# shelves_v05.net
KiCad netlist of a schematic drawn in EAGLE
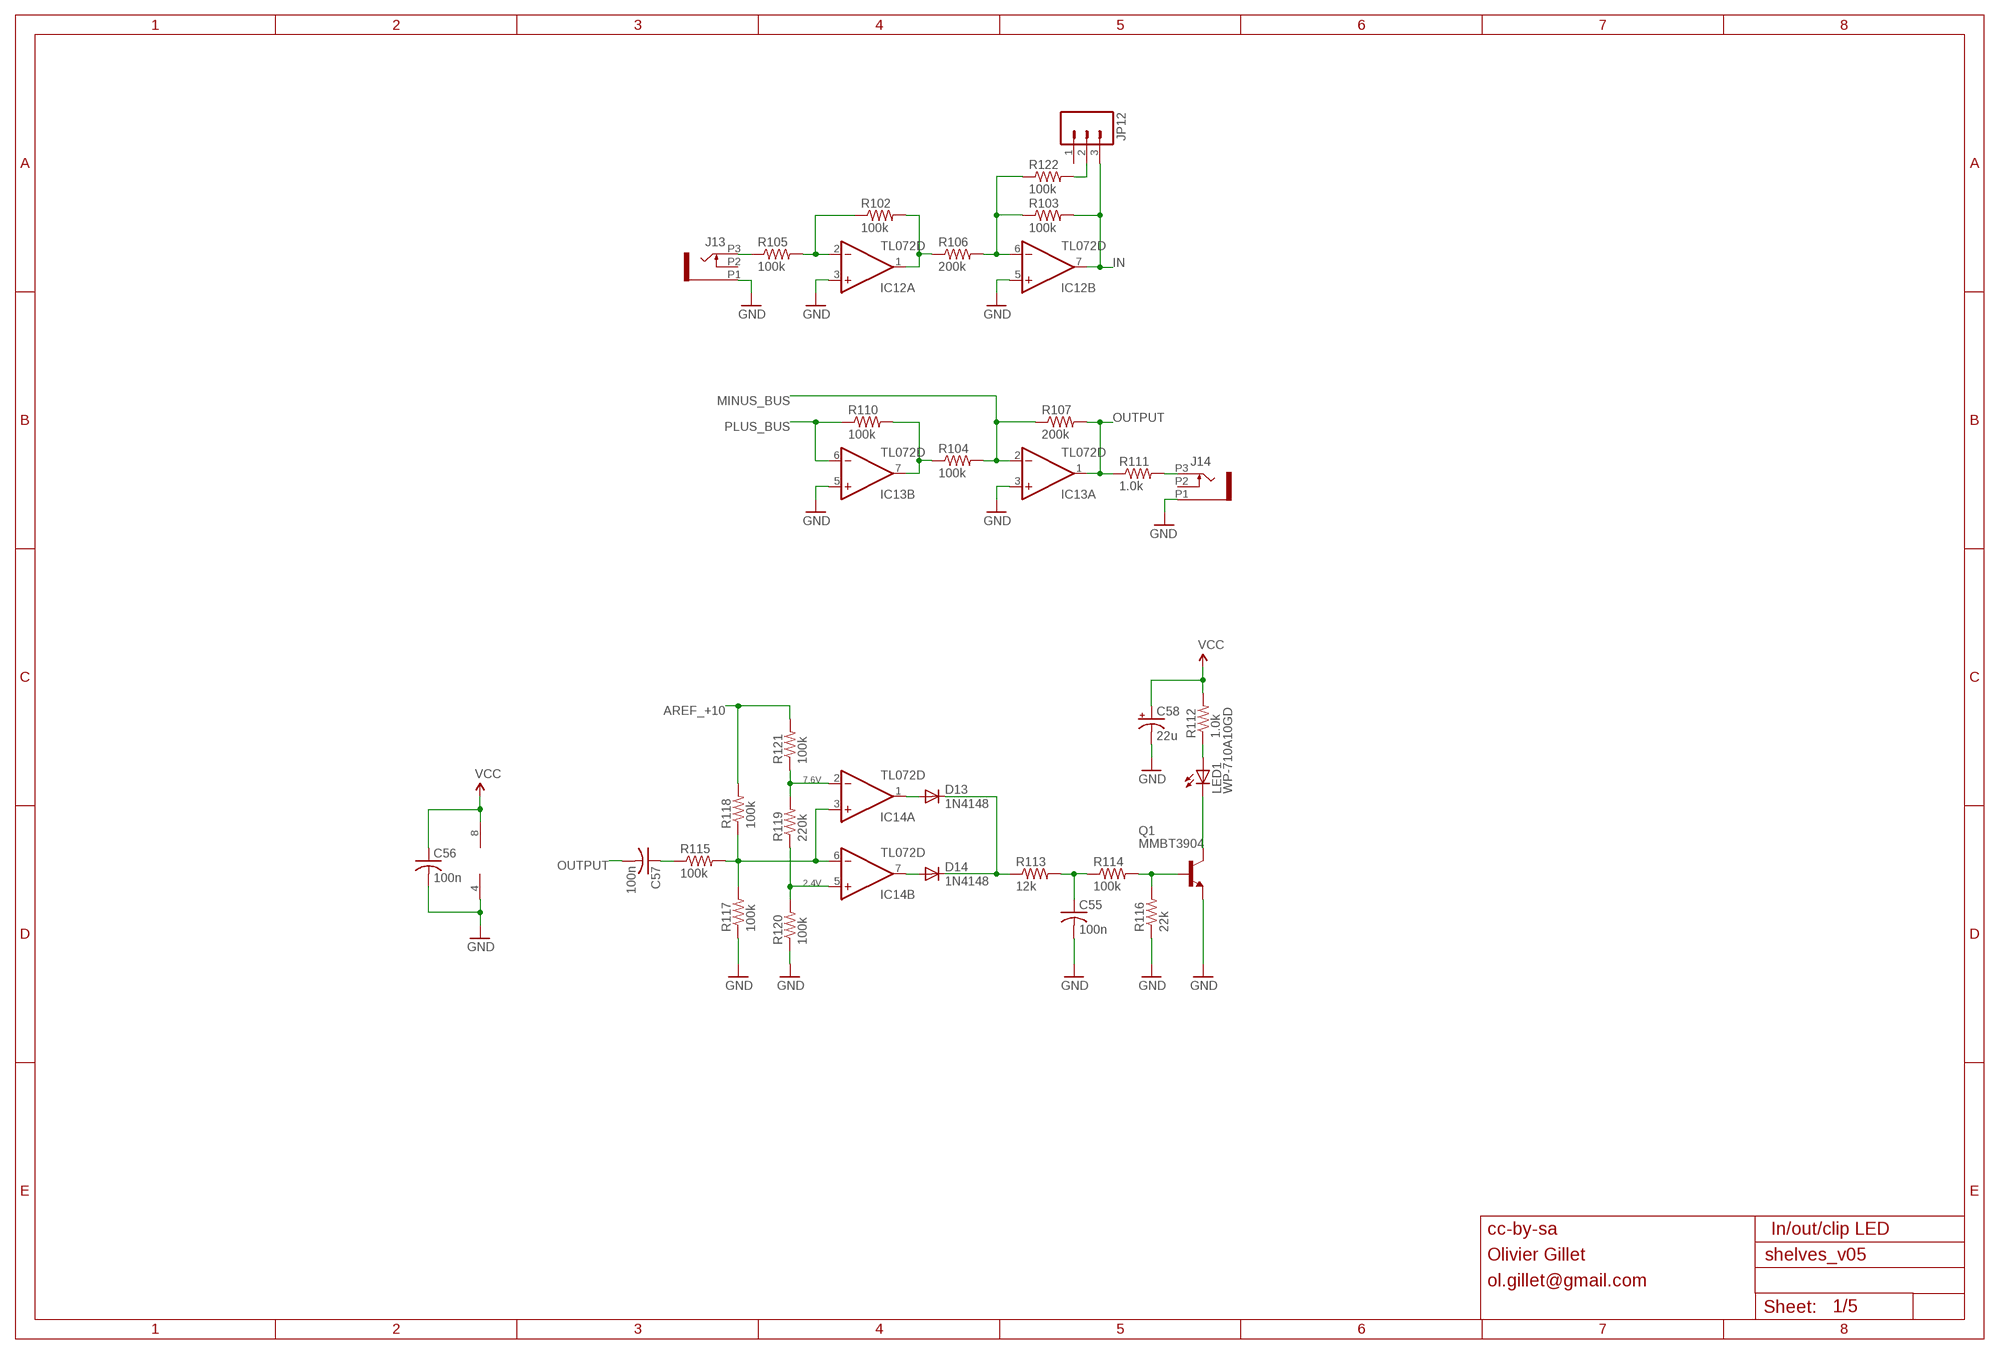
[diagram p0: schematic, sheet 1]
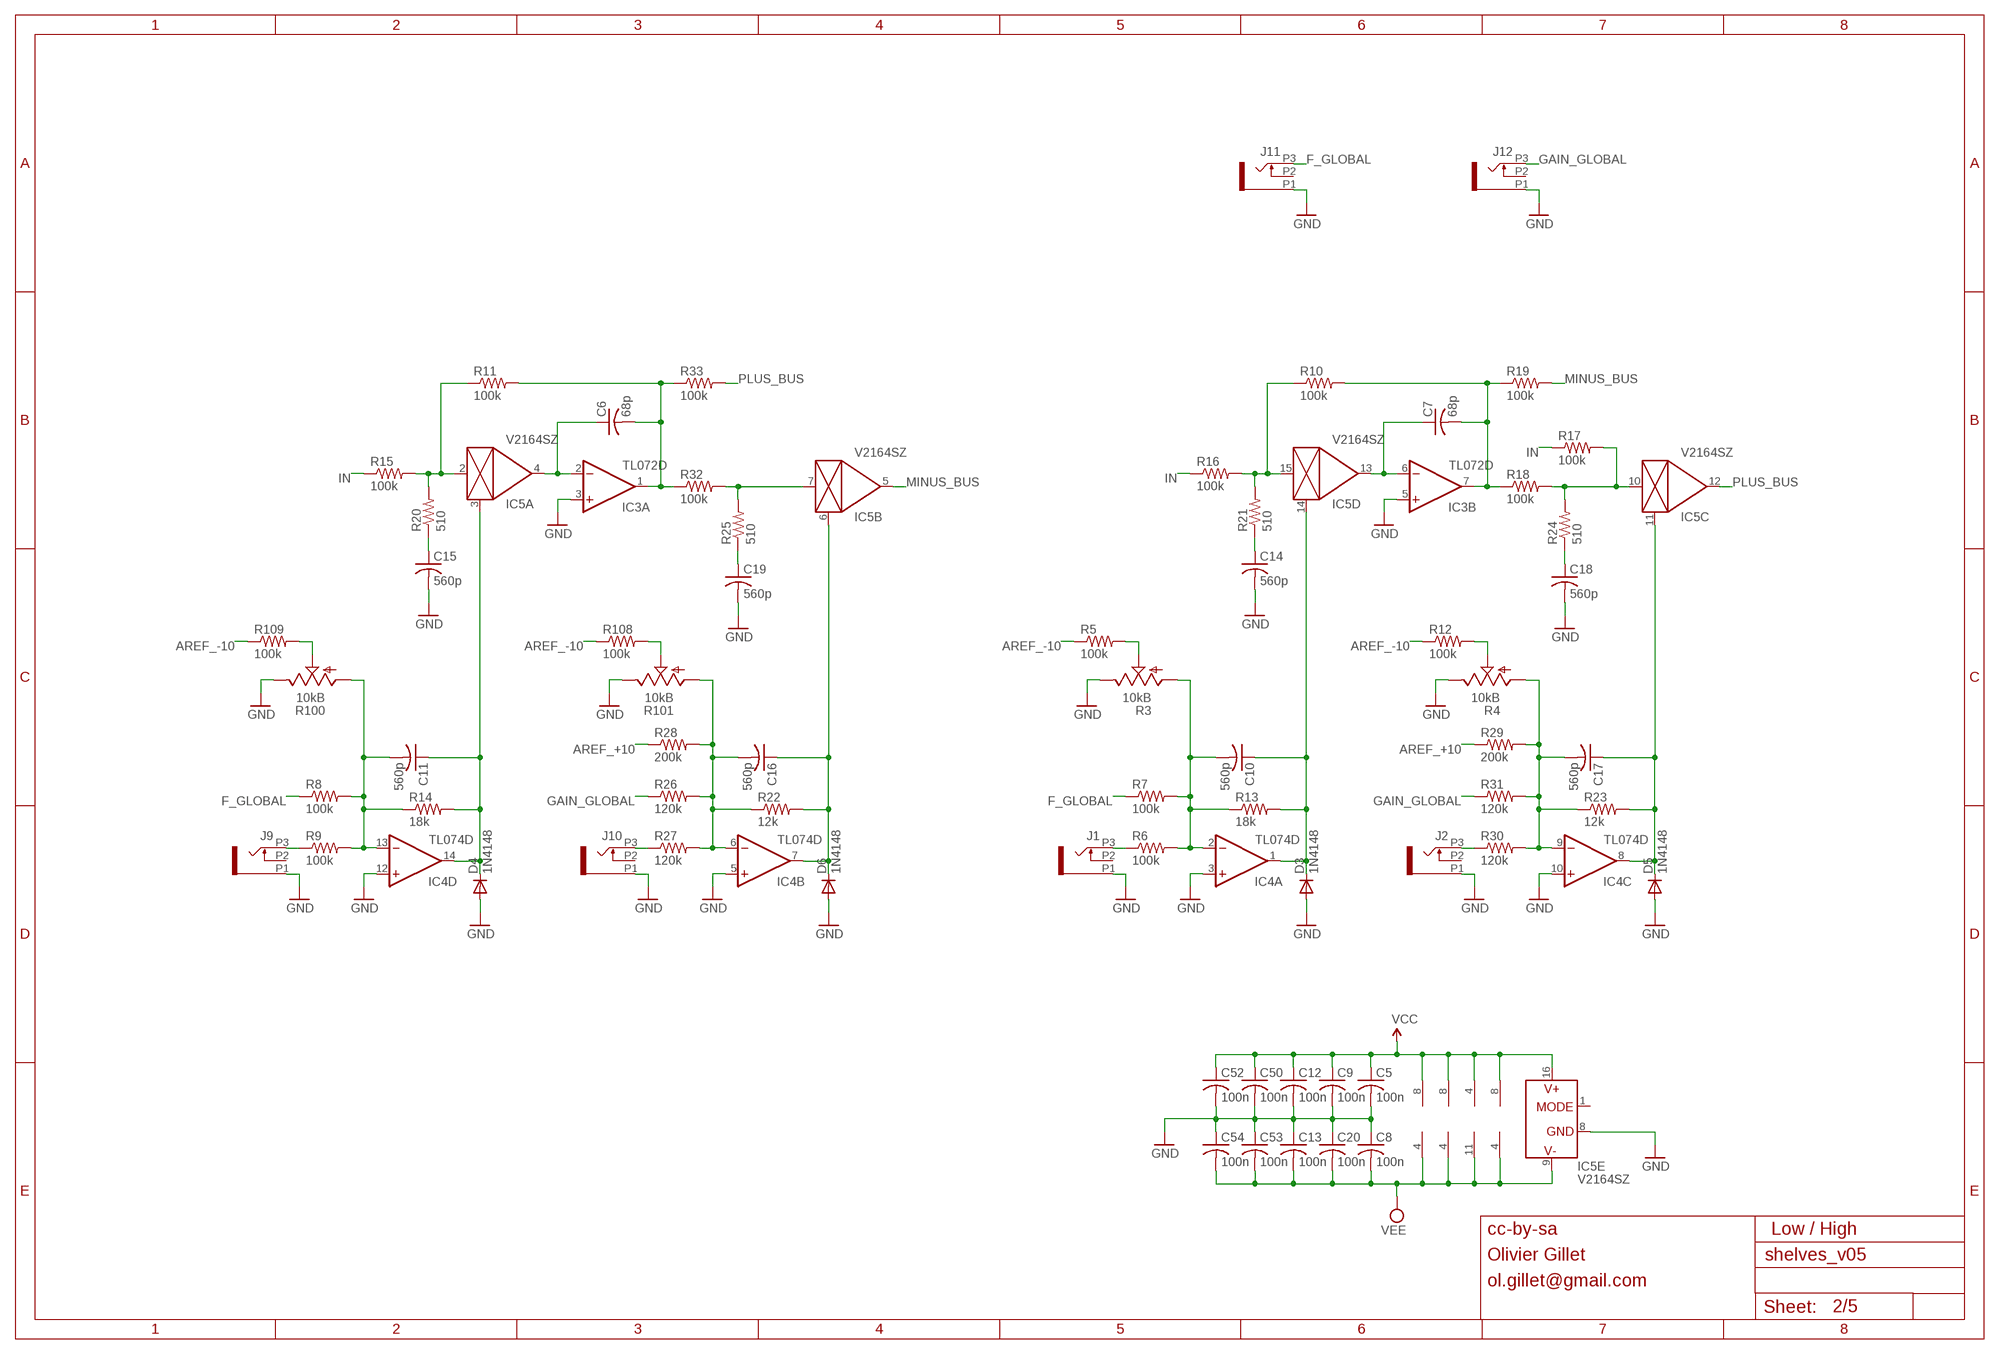
[diagram p1: schematic, sheet 2]
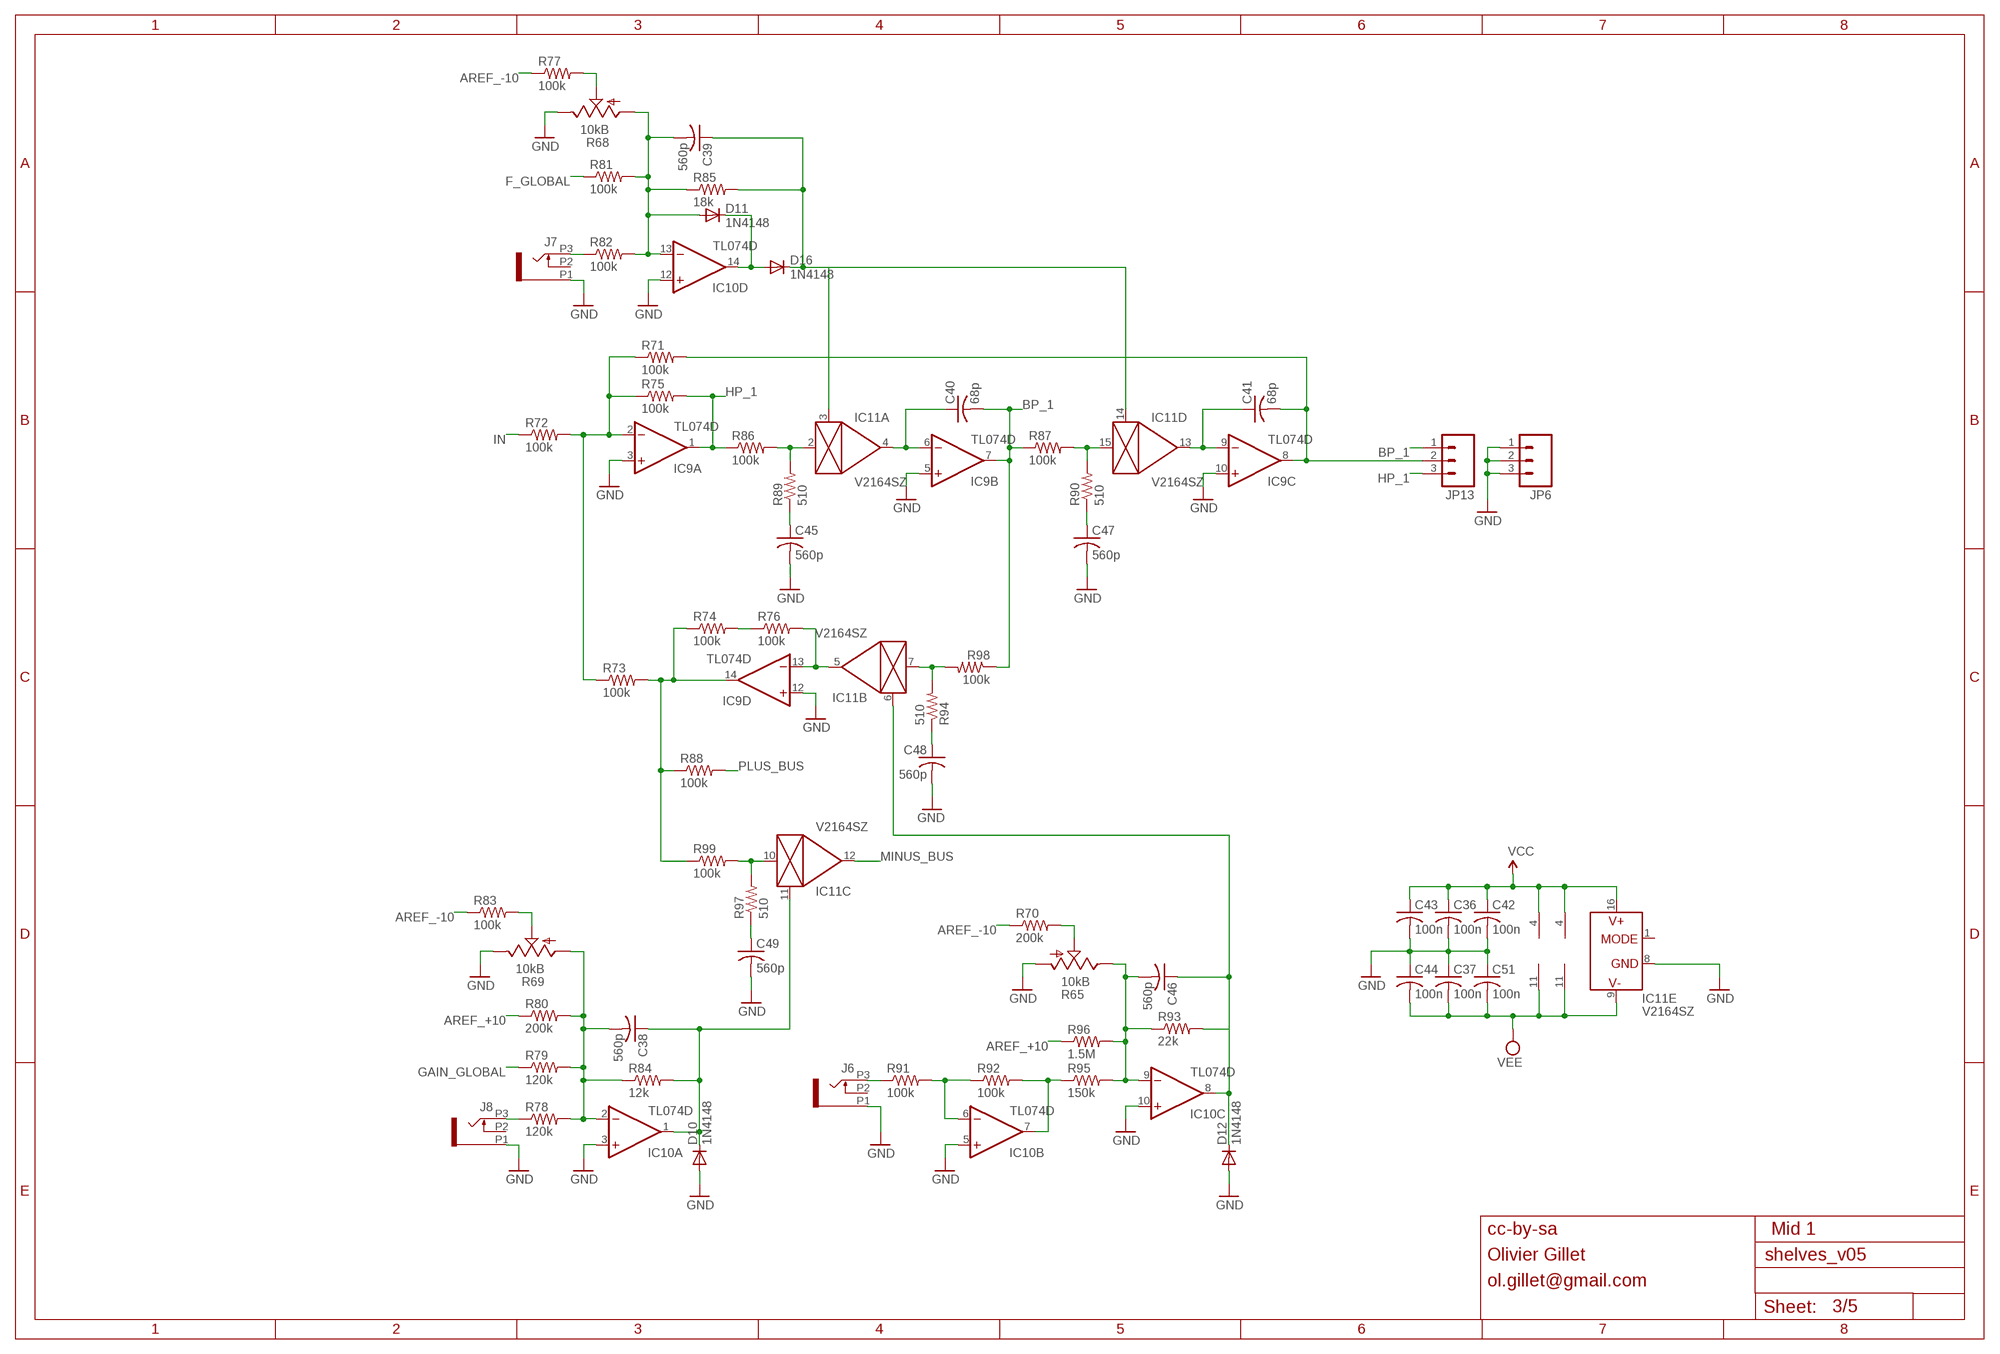
[diagram p2: schematic, sheet 3]
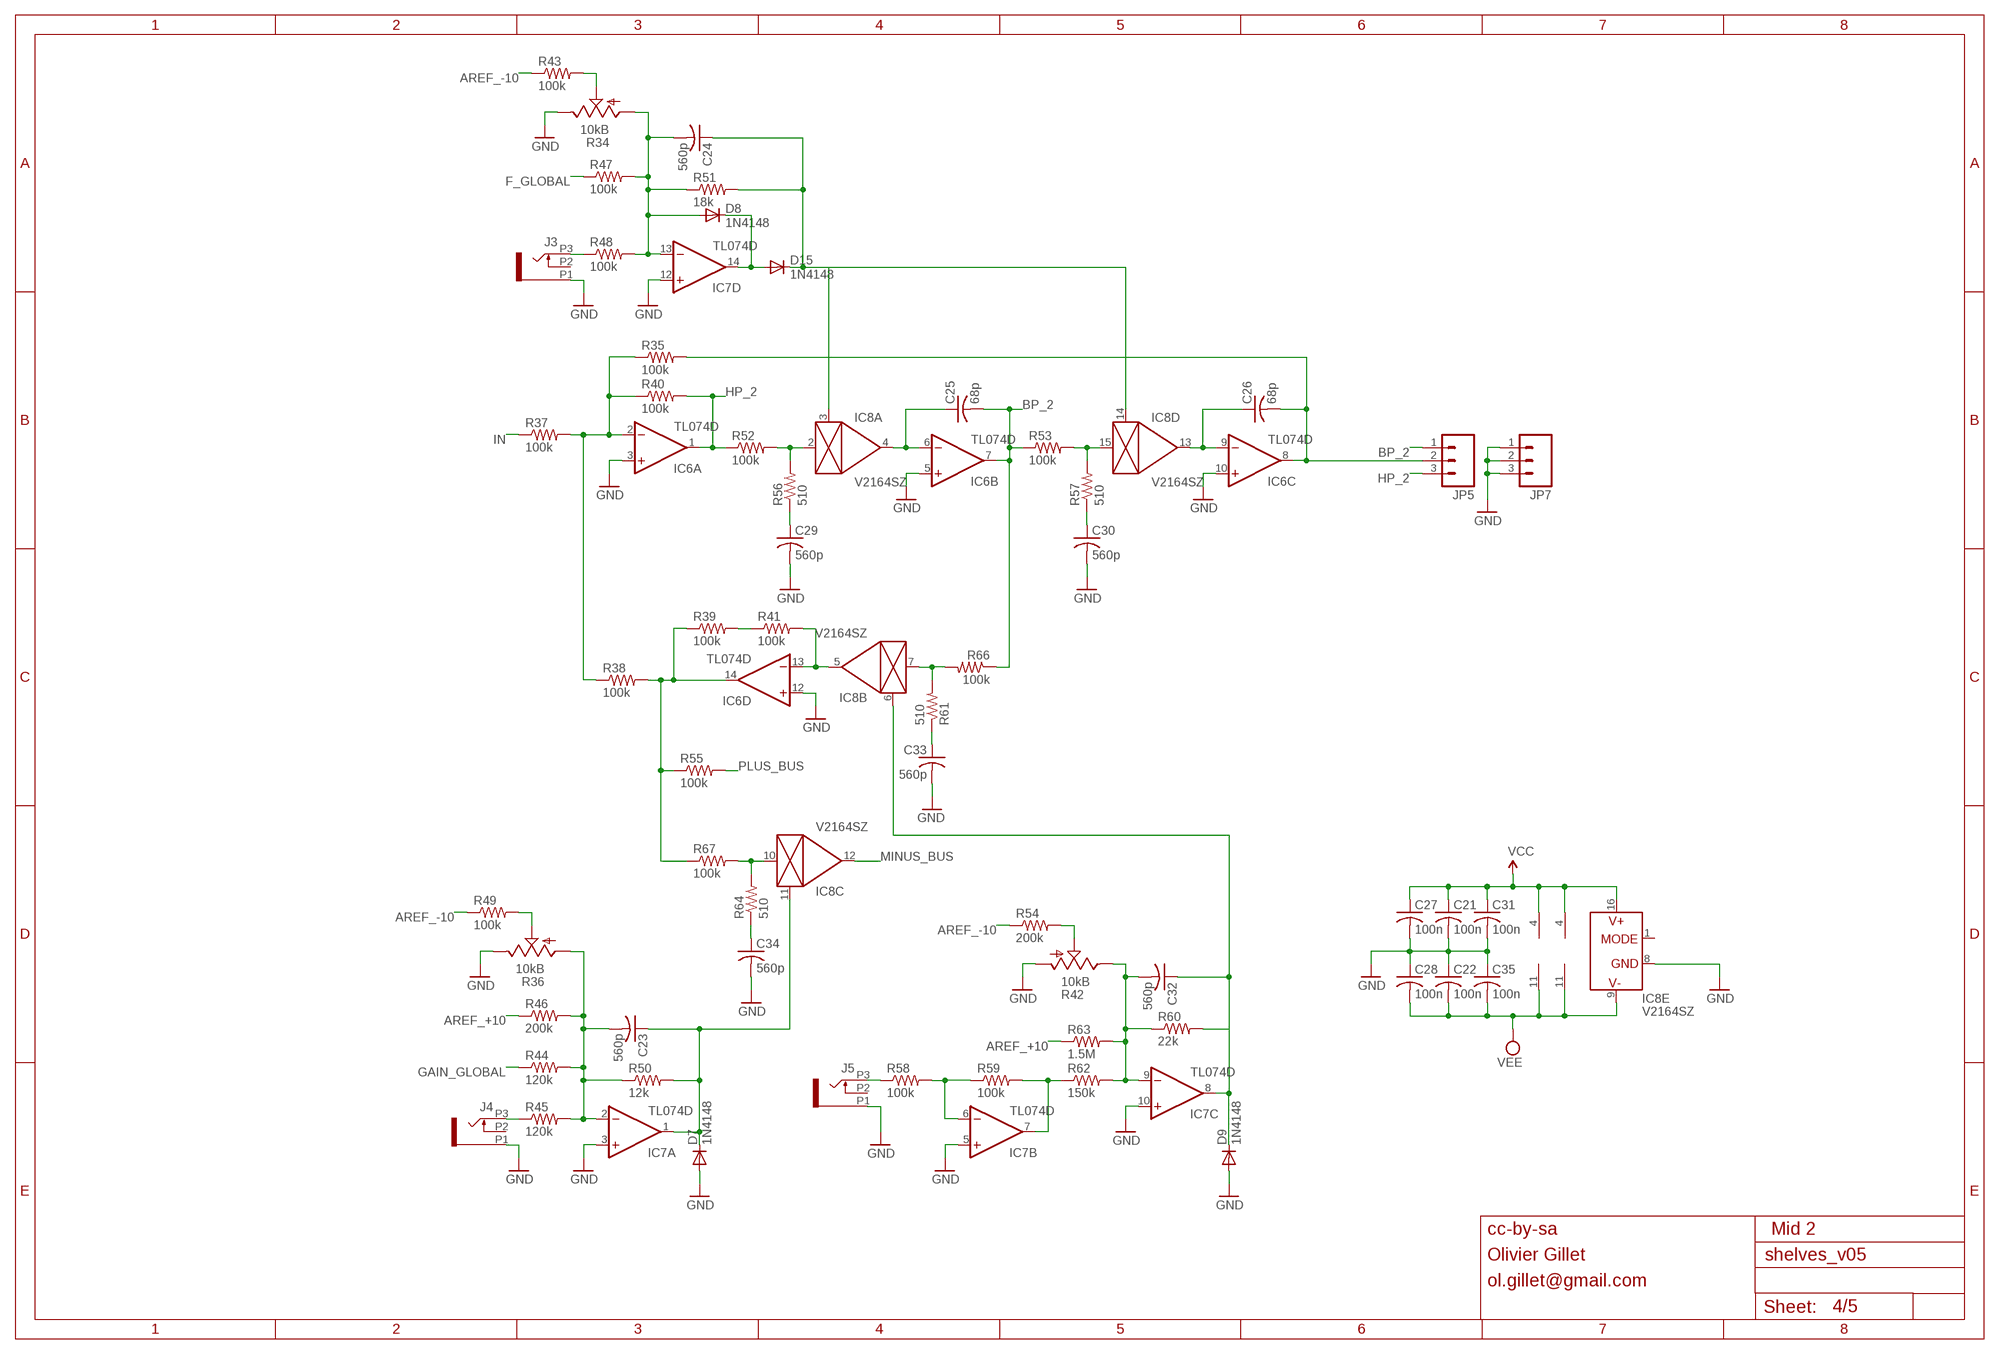
[diagram p3: schematic, sheet 4]
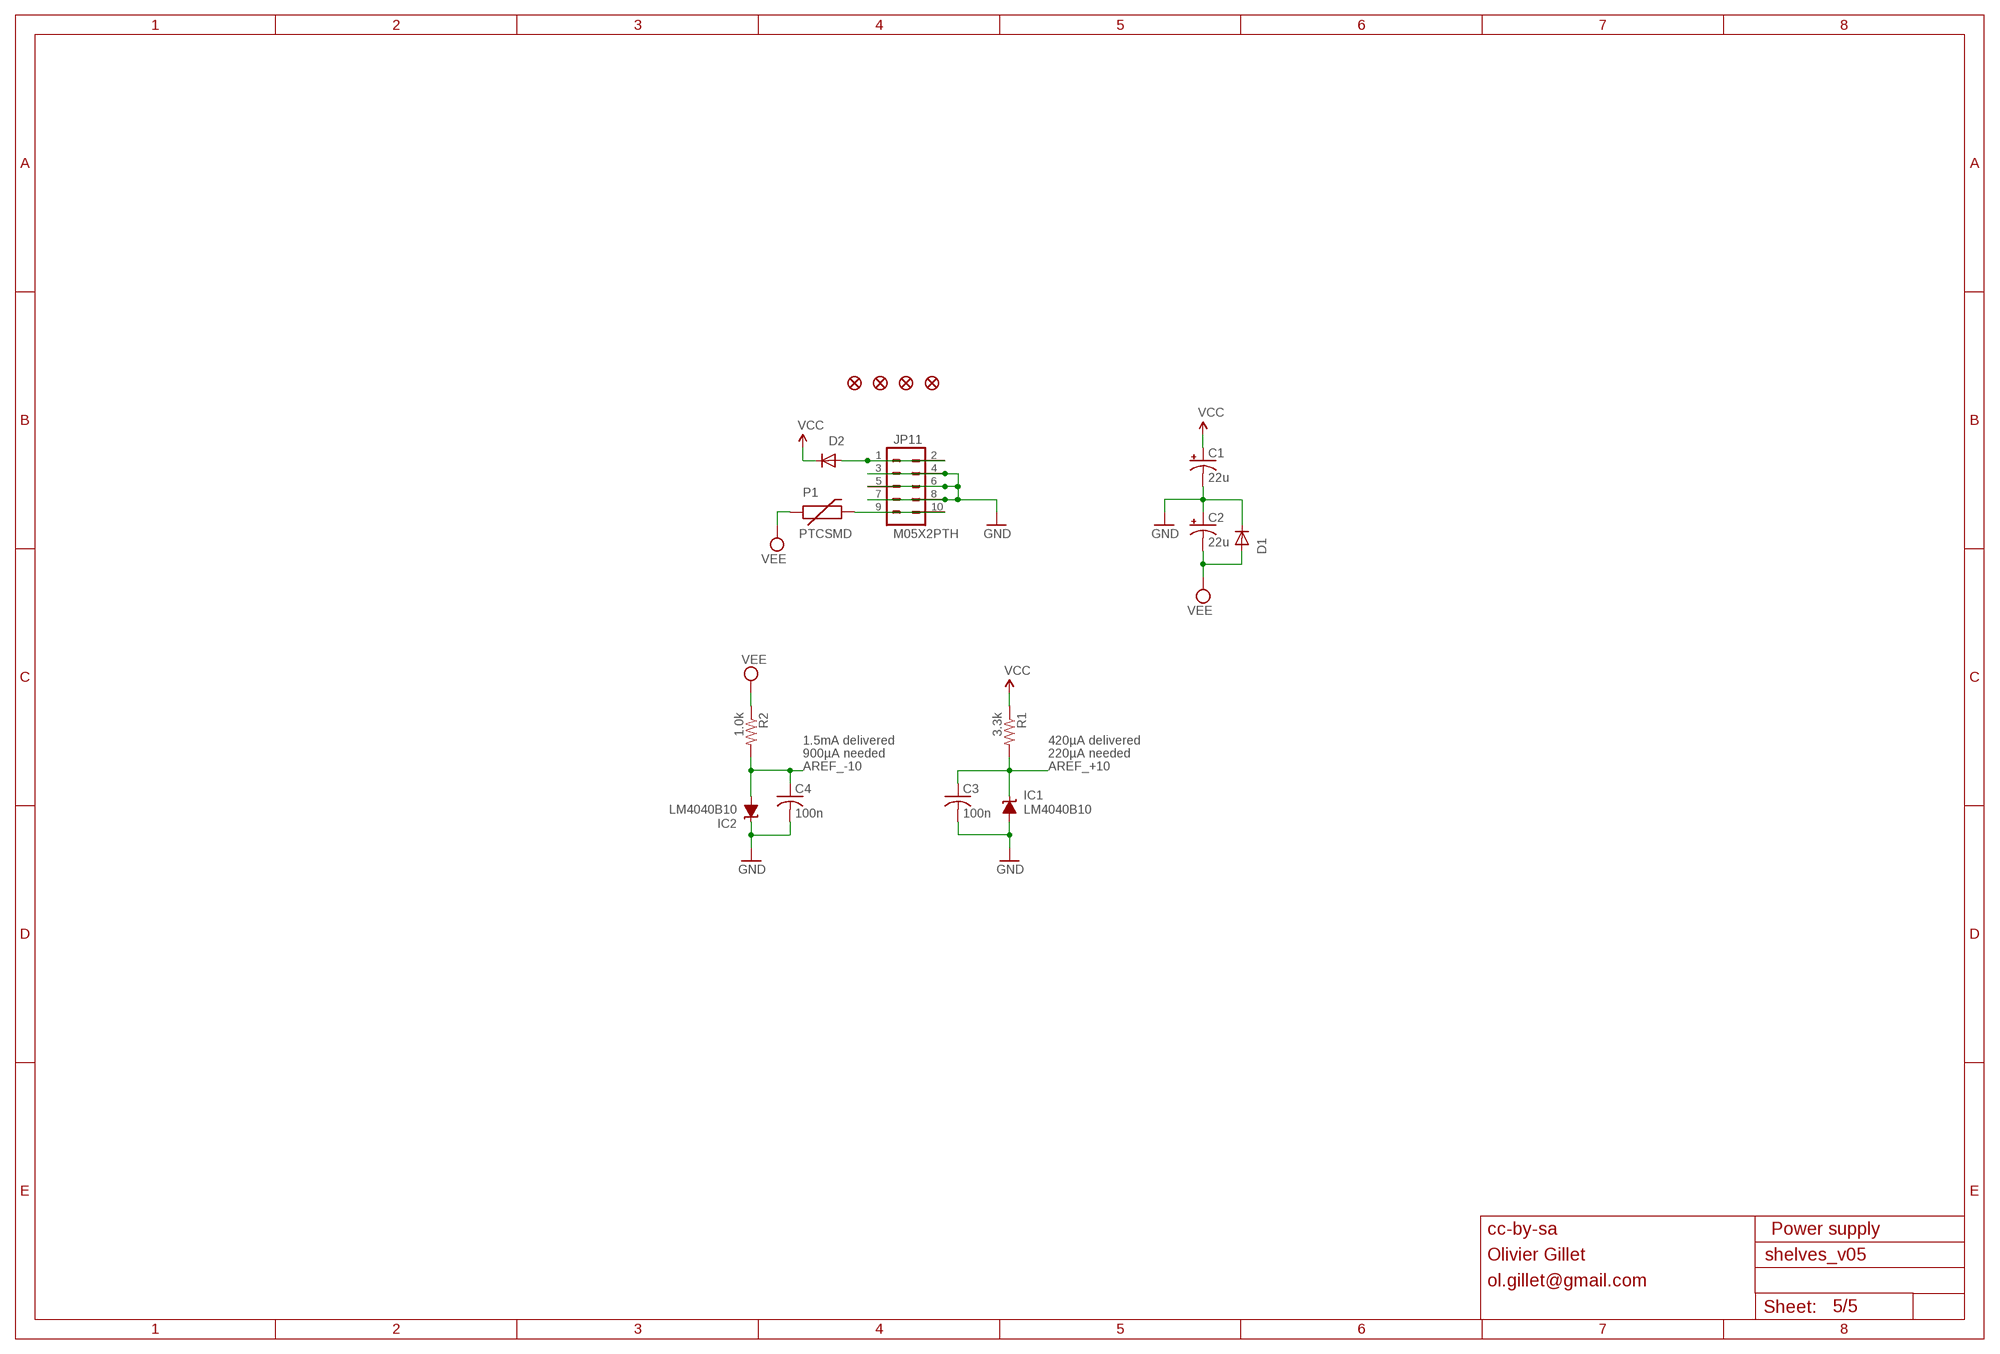
[diagram p4: schematic, sheet 5]

(export (version "E")
  (design (tool "Eeschema 10.0.6"))
  (components
    (comp (ref "C55")
      (value "100n")
      (footprint "eagle-import:C0603")
      (libsource (lib "eagle-import") (part "C-USC0603"))
    )
    (comp (ref "C56")
      (value "100n")
      (footprint "eagle-import:C0603")
      (libsource (lib "eagle-import") (part "C-USC0603"))
    )
    (comp (ref "C57")
      (value "100n")
      (footprint "eagle-import:C0603")
      (libsource (lib "eagle-import") (part "C-USC0603"))
    )
    (comp (ref "C58")
      (value "22u")
      (footprint "eagle-import:PANASONIC_C")
      (libsource (lib "eagle-import") (part "CPOL-USC"))
    )
    (comp (ref "D13")
      (value "1N4148")
      (footprint "eagle-import:SOD323-W")
      (libsource (lib "eagle-import") (part "DIODE-SOD323-W"))
    )
    (comp (ref "D14")
      (value "1N4148")
      (footprint "eagle-import:SOD323-W")
      (libsource (lib "eagle-import") (part "DIODE-SOD323-W"))
    )
    (comp (ref "IC12")
      (value "TL072D")
      (footprint "eagle-import:SO08")
      (libsource (lib "eagle-import") (part "TL072D"))
    )
    (comp (ref "IC13")
      (value "TL072D")
      (footprint "eagle-import:SO08")
      (libsource (lib "eagle-import") (part "TL072D"))
    )
    (comp (ref "IC14")
      (value "TL072D")
      (footprint "eagle-import:SO08")
      (libsource (lib "eagle-import") (part "TL072D"))
    )
    (comp (ref "J13")
      (value "PJ301_THONKICONN6")
      (footprint "eagle-import:WQP_PJ_301M6")
      (libsource (lib "eagle-import") (part "PJ301_THONKICONN6"))
    )
    (comp (ref "J14")
      (value "PJ301_THONKICONN6")
      (footprint "eagle-import:WQP_PJ_301M6")
      (libsource (lib "eagle-import") (part "PJ301_THONKICONN6"))
    )
    (comp (ref "JP12")
      (value "M03PTH")
      (footprint "eagle-import:1X03")
      (libsource (lib "eagle-import") (part "M03PTH"))
    )
    (comp (ref "LED1")
      (value "WP-710A10GD")
      (footprint "eagle-import:LED3MM")
      (libsource (lib "eagle-import") (part "LED3MM"))
    )
    (comp (ref "Q1")
      (value "MMBT3904")
      (footprint "eagle-import:SOT23-BEC")
      (libsource (lib "eagle-import") (part "-NPN-SOT23-BECMMBT3904LT1"))
    )
    (comp (ref "R102")
      (value "100k")
      (footprint "eagle-import:R0603")
      (libsource (lib "eagle-import") (part "R-US_R0603"))
    )
    (comp (ref "R103")
      (value "100k")
      (footprint "eagle-import:R0603")
      (libsource (lib "eagle-import") (part "R-US_R0603"))
    )
    (comp (ref "R104")
      (value "100k")
      (footprint "eagle-import:R0603")
      (libsource (lib "eagle-import") (part "R-US_R0603"))
    )
    (comp (ref "R105")
      (value "100k")
      (footprint "eagle-import:R0603")
      (libsource (lib "eagle-import") (part "R-US_R0603"))
    )
    (comp (ref "R106")
      (value "200k")
      (footprint "eagle-import:R0603")
      (libsource (lib "eagle-import") (part "R-US_R0603"))
    )
    (comp (ref "R107")
      (value "200k")
      (footprint "eagle-import:R0603")
      (libsource (lib "eagle-import") (part "R-US_R0603"))
    )
    (comp (ref "R110")
      (value "100k")
      (footprint "eagle-import:R0603")
      (libsource (lib "eagle-import") (part "R-US_R0603"))
    )
    (comp (ref "R111")
      (value "1.0k")
      (footprint "eagle-import:R0603")
      (libsource (lib "eagle-import") (part "R-US_R0603"))
    )
    (comp (ref "R112")
      (value "1.0k")
      (footprint "eagle-import:R0603")
      (libsource (lib "eagle-import") (part "R-US_R0603"))
    )
    (comp (ref "R113")
      (value "12k")
      (footprint "eagle-import:R0603")
      (libsource (lib "eagle-import") (part "R-US_R0603"))
    )
    (comp (ref "R114")
      (value "100k")
      (footprint "eagle-import:R0603")
      (libsource (lib "eagle-import") (part "R-US_R0603"))
    )
    (comp (ref "R115")
      (value "100k")
      (footprint "eagle-import:R0603")
      (libsource (lib "eagle-import") (part "R-US_R0603"))
    )
    (comp (ref "R116")
      (value "22k")
      (footprint "eagle-import:R0603")
      (libsource (lib "eagle-import") (part "R-US_R0603"))
    )
    (comp (ref "R117")
      (value "100k")
      (footprint "eagle-import:R0603")
      (libsource (lib "eagle-import") (part "R-US_R0603"))
    )
    (comp (ref "R118")
      (value "100k")
      (footprint "eagle-import:R0603")
      (libsource (lib "eagle-import") (part "R-US_R0603"))
    )
    (comp (ref "R119")
      (value "220k")
      (footprint "eagle-import:R0603")
      (libsource (lib "eagle-import") (part "R-US_R0603"))
    )
    (comp (ref "R120")
      (value "100k")
      (footprint "eagle-import:R0603")
      (libsource (lib "eagle-import") (part "R-US_R0603"))
    )
    (comp (ref "R121")
      (value "100k")
      (footprint "eagle-import:R0603")
      (libsource (lib "eagle-import") (part "R-US_R0603"))
    )
    (comp (ref "R122")
      (value "100k")
      (footprint "eagle-import:R0603")
      (libsource (lib "eagle-import") (part "R-US_R0603"))
    )
    (comp (ref "C21")
      (value "100n")
      (footprint "eagle-import:C0603")
      (libsource (lib "eagle-import") (part "C-USC0603"))
    )
    (comp (ref "C22")
      (value "100n")
      (footprint "eagle-import:C0603")
      (libsource (lib "eagle-import") (part "C-USC0603"))
    )
    (comp (ref "C23")
      (value "560p")
      (footprint "eagle-import:C0603")
      (libsource (lib "eagle-import") (part "C-USC0603"))
    )
    (comp (ref "C24")
      (value "560p")
      (footprint "eagle-import:C0603")
      (libsource (lib "eagle-import") (part "C-USC0603"))
    )
    (comp (ref "C25")
      (value "68p")
      (footprint "eagle-import:C0603")
      (libsource (lib "eagle-import") (part "C-USC0603"))
    )
    (comp (ref "C26")
      (value "68p")
      (footprint "eagle-import:C0603")
      (libsource (lib "eagle-import") (part "C-USC0603"))
    )
    (comp (ref "C27")
      (value "100n")
      (footprint "eagle-import:C0603")
      (libsource (lib "eagle-import") (part "C-USC0603"))
    )
    (comp (ref "C28")
      (value "100n")
      (footprint "eagle-import:C0603")
      (libsource (lib "eagle-import") (part "C-USC0603"))
    )
    (comp (ref "C29")
      (value "560p")
      (footprint "eagle-import:C0603")
      (libsource (lib "eagle-import") (part "C-USC0603"))
    )
    (comp (ref "C30")
      (value "560p")
      (footprint "eagle-import:C0603")
      (libsource (lib "eagle-import") (part "C-USC0603"))
    )
    (comp (ref "C31")
      (value "100n")
      (footprint "eagle-import:C0603")
      (libsource (lib "eagle-import") (part "C-USC0603"))
    )
    (comp (ref "C32")
      (value "560p")
      (footprint "eagle-import:C0603")
      (libsource (lib "eagle-import") (part "C-USC0603"))
    )
    (comp (ref "C33")
      (value "560p")
      (footprint "eagle-import:C0603")
      (libsource (lib "eagle-import") (part "C-USC0603"))
    )
    (comp (ref "C34")
      (value "560p")
      (footprint "eagle-import:C0603")
      (libsource (lib "eagle-import") (part "C-USC0603"))
    )
    (comp (ref "C35")
      (value "100n")
      (footprint "eagle-import:C0603")
      (libsource (lib "eagle-import") (part "C-USC0603"))
    )
    (comp (ref "D7")
      (value "1N4148")
      (footprint "eagle-import:SOD323-W")
      (libsource (lib "eagle-import") (part "DIODE-SOD323-W"))
    )
    (comp (ref "D8")
      (value "1N4148")
      (footprint "eagle-import:SOD323-W")
      (libsource (lib "eagle-import") (part "DIODE-SOD323-W"))
    )
    (comp (ref "D9")
      (value "1N4148")
      (footprint "eagle-import:SOD323-W")
      (libsource (lib "eagle-import") (part "DIODE-SOD323-W"))
    )
    (comp (ref "D15")
      (value "1N4148")
      (footprint "eagle-import:SOD323-W")
      (libsource (lib "eagle-import") (part "DIODE-SOD323-W"))
    )
    (comp (ref "IC6")
      (value "TL074D")
      (footprint "eagle-import:SO14")
      (libsource (lib "eagle-import") (part "TL074D"))
    )
    (comp (ref "IC7")
      (value "TL074D")
      (footprint "eagle-import:SO14")
      (libsource (lib "eagle-import") (part "TL074D"))
    )
    (comp (ref "IC8")
      (value "V2164SZ")
      (footprint "eagle-import:SOIC16N")
      (libsource (lib "eagle-import") (part "SSM2164S"))
    )
    (comp (ref "J3")
      (value "PJ301_THONKICONN6")
      (footprint "eagle-import:WQP_PJ_301M6")
      (libsource (lib "eagle-import") (part "PJ301_THONKICONN6"))
    )
    (comp (ref "J4")
      (value "PJ301_THONKICONN6")
      (footprint "eagle-import:WQP_PJ_301M6")
      (libsource (lib "eagle-import") (part "PJ301_THONKICONN6"))
    )
    (comp (ref "J5")
      (value "PJ301_THONKICONN6")
      (footprint "eagle-import:WQP_PJ_301M6")
      (libsource (lib "eagle-import") (part "PJ301_THONKICONN6"))
    )
    (comp (ref "JP5")
      (value "M03PTH")
      (footprint "eagle-import:1X03")
      (libsource (lib "eagle-import") (part "M03PTH"))
    )
    (comp (ref "JP7")
      (value "M03PTH")
      (footprint "eagle-import:1X03")
      (libsource (lib "eagle-import") (part "M03PTH"))
    )
    (comp (ref "R34")
      (value "10kB")
      (footprint "eagle-import:ALPS_POT_VERTICAL_PS")
      (libsource (lib "eagle-import") (part "POT_USVERTICAL_PS"))
    )
    (comp (ref "R35")
      (value "100k")
      (footprint "eagle-import:R0603")
      (libsource (lib "eagle-import") (part "R-US_R0603"))
    )
    (comp (ref "R36")
      (value "10kB")
      (footprint "eagle-import:ALPS_POT_VERTICAL_PS")
      (libsource (lib "eagle-import") (part "POT_USVERTICAL_PS"))
    )
    (comp (ref "R37")
      (value "100k")
      (footprint "eagle-import:R0603")
      (libsource (lib "eagle-import") (part "R-US_R0603"))
    )
    (comp (ref "R38")
      (value "100k")
      (footprint "eagle-import:R0603")
      (libsource (lib "eagle-import") (part "R-US_R0603"))
    )
    (comp (ref "R39")
      (value "100k")
      (footprint "eagle-import:R0603")
      (libsource (lib "eagle-import") (part "R-US_R0603"))
    )
    (comp (ref "R40")
      (value "100k")
      (footprint "eagle-import:R0603")
      (libsource (lib "eagle-import") (part "R-US_R0603"))
    )
    (comp (ref "R41")
      (value "100k")
      (footprint "eagle-import:R0603")
      (libsource (lib "eagle-import") (part "R-US_R0603"))
    )
    (comp (ref "R42")
      (value "10kB")
      (footprint "eagle-import:ALPS_POT_VERTICAL")
      (libsource (lib "eagle-import") (part "POT_USVERTICAL"))
    )
    (comp (ref "R43")
      (value "100k")
      (footprint "eagle-import:R0603")
      (libsource (lib "eagle-import") (part "R-US_R0603"))
    )
    (comp (ref "R44")
      (value "120k")
      (footprint "eagle-import:R0603")
      (libsource (lib "eagle-import") (part "R-US_R0603"))
    )
    (comp (ref "R45")
      (value "120k")
      (footprint "eagle-import:R0603")
      (libsource (lib "eagle-import") (part "R-US_R0603"))
    )
    (comp (ref "R46")
      (value "200k")
      (footprint "eagle-import:R0603")
      (libsource (lib "eagle-import") (part "R-US_R0603"))
    )
    (comp (ref "R47")
      (value "100k")
      (footprint "eagle-import:R0603")
      (libsource (lib "eagle-import") (part "R-US_R0603"))
    )
    (comp (ref "R48")
      (value "100k")
      (footprint "eagle-import:R0603")
      (libsource (lib "eagle-import") (part "R-US_R0603"))
    )
    (comp (ref "R49")
      (value "100k")
      (footprint "eagle-import:R0603")
      (libsource (lib "eagle-import") (part "R-US_R0603"))
    )
    (comp (ref "R50")
      (value "12k")
      (footprint "eagle-import:R0603")
      (libsource (lib "eagle-import") (part "R-US_R0603"))
    )
    (comp (ref "R51")
      (value "18k")
      (footprint "eagle-import:R0603")
      (libsource (lib "eagle-import") (part "R-US_R0603"))
    )
    (comp (ref "R52")
      (value "100k")
      (footprint "eagle-import:R0603")
      (libsource (lib "eagle-import") (part "R-US_R0603"))
    )
    (comp (ref "R53")
      (value "100k")
      (footprint "eagle-import:R0603")
      (libsource (lib "eagle-import") (part "R-US_R0603"))
    )
    (comp (ref "R54")
      (value "200k")
      (footprint "eagle-import:R0603")
      (libsource (lib "eagle-import") (part "R-US_R0603"))
    )
    (comp (ref "R55")
      (value "100k")
      (footprint "eagle-import:R0603")
      (libsource (lib "eagle-import") (part "R-US_R0603"))
    )
    (comp (ref "R56")
      (value "510")
      (footprint "eagle-import:R0603")
      (libsource (lib "eagle-import") (part "R-US_R0603"))
    )
    (comp (ref "R57")
      (value "510")
      (footprint "eagle-import:R0603")
      (libsource (lib "eagle-import") (part "R-US_R0603"))
    )
    (comp (ref "R58")
      (value "100k")
      (footprint "eagle-import:R0603")
      (libsource (lib "eagle-import") (part "R-US_R0603"))
    )
    (comp (ref "R59")
      (value "100k")
      (footprint "eagle-import:R0603")
      (libsource (lib "eagle-import") (part "R-US_R0603"))
    )
    (comp (ref "R60")
      (value "22k")
      (footprint "eagle-import:R0603")
      (libsource (lib "eagle-import") (part "R-US_R0603"))
    )
    (comp (ref "R61")
      (value "510")
      (footprint "eagle-import:R0603")
      (libsource (lib "eagle-import") (part "R-US_R0603"))
    )
    (comp (ref "R62")
      (value "150k")
      (footprint "eagle-import:R0603")
      (libsource (lib "eagle-import") (part "R-US_R0603"))
    )
    (comp (ref "R63")
      (value "1.5M")
      (footprint "eagle-import:R0603")
      (libsource (lib "eagle-import") (part "R-US_R0603"))
    )
    (comp (ref "R64")
      (value "510")
      (footprint "eagle-import:R0603")
      (libsource (lib "eagle-import") (part "R-US_R0603"))
    )
    (comp (ref "R66")
      (value "100k")
      (footprint "eagle-import:R0603")
      (libsource (lib "eagle-import") (part "R-US_R0603"))
    )
    (comp (ref "R67")
      (value "100k")
      (footprint "eagle-import:R0603")
      (libsource (lib "eagle-import") (part "R-US_R0603"))
    )
    (comp (ref "C5")
      (value "100n")
      (footprint "eagle-import:C0603")
      (libsource (lib "eagle-import") (part "C-USC0603"))
    )
    (comp (ref "C6")
      (value "68p")
      (footprint "eagle-import:C0603")
      (libsource (lib "eagle-import") (part "C-USC0603"))
    )
    (comp (ref "C7")
      (value "68p")
      (footprint "eagle-import:C0603")
      (libsource (lib "eagle-import") (part "C-USC0603"))
    )
    (comp (ref "C8")
      (value "100n")
      (footprint "eagle-import:C0603")
      (libsource (lib "eagle-import") (part "C-USC0603"))
    )
    (comp (ref "C9")
      (value "100n")
      (footprint "eagle-import:C0603")
      (libsource (lib "eagle-import") (part "C-USC0603"))
    )
    (comp (ref "C10")
      (value "560p")
      (footprint "eagle-import:C0603")
      (libsource (lib "eagle-import") (part "C-USC0603"))
    )
    (comp (ref "C11")
      (value "560p")
      (footprint "eagle-import:C0603")
      (libsource (lib "eagle-import") (part "C-USC0603"))
    )
    (comp (ref "C12")
      (value "100n")
      (footprint "eagle-import:C0603")
      (libsource (lib "eagle-import") (part "C-USC0603"))
    )
    (comp (ref "C13")
      (value "100n")
      (footprint "eagle-import:C0603")
      (libsource (lib "eagle-import") (part "C-USC0603"))
    )
    (comp (ref "C14")
      (value "560p")
      (footprint "eagle-import:C0603")
      (libsource (lib "eagle-import") (part "C-USC0603"))
    )
    (comp (ref "C15")
      (value "560p")
      (footprint "eagle-import:C0603")
      (libsource (lib "eagle-import") (part "C-USC0603"))
    )
    (comp (ref "C16")
      (value "560p")
      (footprint "eagle-import:C0603")
      (libsource (lib "eagle-import") (part "C-USC0603"))
    )
    (comp (ref "C17")
      (value "560p")
      (footprint "eagle-import:C0603")
      (libsource (lib "eagle-import") (part "C-USC0603"))
    )
    (comp (ref "C18")
      (value "560p")
      (footprint "eagle-import:C0603")
      (libsource (lib "eagle-import") (part "C-USC0603"))
    )
    (comp (ref "C19")
      (value "560p")
      (footprint "eagle-import:C0603")
      (libsource (lib "eagle-import") (part "C-USC0603"))
    )
    (comp (ref "C20")
      (value "100n")
      (footprint "eagle-import:C0603")
      (libsource (lib "eagle-import") (part "C-USC0603"))
    )
    (comp (ref "C50")
      (value "100n")
      (footprint "eagle-import:C0603")
      (libsource (lib "eagle-import") (part "C-USC0603"))
    )
    (comp (ref "C52")
      (value "100n")
      (footprint "eagle-import:C0603")
      (libsource (lib "eagle-import") (part "C-USC0603"))
    )
    (comp (ref "C53")
      (value "100n")
      (footprint "eagle-import:C0603")
      (libsource (lib "eagle-import") (part "C-USC0603"))
    )
    (comp (ref "C54")
      (value "100n")
      (footprint "eagle-import:C0603")
      (libsource (lib "eagle-import") (part "C-USC0603"))
    )
    (comp (ref "D3")
      (value "1N4148")
      (footprint "eagle-import:SOD323-W")
      (libsource (lib "eagle-import") (part "DIODE-SOD323-W"))
    )
    (comp (ref "D4")
      (value "1N4148")
      (footprint "eagle-import:SOD323-W")
      (libsource (lib "eagle-import") (part "DIODE-SOD323-W"))
    )
    (comp (ref "D5")
      (value "1N4148")
      (footprint "eagle-import:SOD323-W")
      (libsource (lib "eagle-import") (part "DIODE-SOD323-W"))
    )
    (comp (ref "D6")
      (value "1N4148")
      (footprint "eagle-import:SOD323-W")
      (libsource (lib "eagle-import") (part "DIODE-SOD323-W"))
    )
    (comp (ref "IC3")
      (value "TL072D")
      (footprint "eagle-import:SO08")
      (libsource (lib "eagle-import") (part "TL072D"))
    )
    (comp (ref "IC4")
      (value "TL074D")
      (footprint "eagle-import:SO14")
      (libsource (lib "eagle-import") (part "TL074D"))
    )
    (comp (ref "IC5")
      (value "V2164SZ")
      (footprint "eagle-import:SOIC16N")
      (libsource (lib "eagle-import") (part "SSM2164S"))
    )
    (comp (ref "J1")
      (value "PJ301_THONKICONN6")
      (footprint "eagle-import:WQP_PJ_301M6")
      (libsource (lib "eagle-import") (part "PJ301_THONKICONN6"))
    )
    (comp (ref "J2")
      (value "PJ301_THONKICONN6")
      (footprint "eagle-import:WQP_PJ_301M6")
      (libsource (lib "eagle-import") (part "PJ301_THONKICONN6"))
    )
    (comp (ref "J9")
      (value "PJ301_THONKICONN6")
      (footprint "eagle-import:WQP_PJ_301M6")
      (libsource (lib "eagle-import") (part "PJ301_THONKICONN6"))
    )
    (comp (ref "J10")
      (value "PJ301_THONKICONN6")
      (footprint "eagle-import:WQP_PJ_301M6")
      (libsource (lib "eagle-import") (part "PJ301_THONKICONN6"))
    )
    (comp (ref "J11")
      (value "PJ301_THONKICONN6")
      (footprint "eagle-import:WQP_PJ_301M6")
      (libsource (lib "eagle-import") (part "PJ301_THONKICONN6"))
    )
    (comp (ref "J12")
      (value "PJ301_THONKICONN6")
      (footprint "eagle-import:WQP_PJ_301M6")
      (libsource (lib "eagle-import") (part "PJ301_THONKICONN6"))
    )
    (comp (ref "R3")
      (value "10kB")
      (footprint "eagle-import:ALPS_POT_VERTICAL_PS")
      (libsource (lib "eagle-import") (part "POT_USVERTICAL_PS"))
    )
    (comp (ref "R4")
      (value "10kB")
      (footprint "eagle-import:ALPS_POT_VERTICAL_PS")
      (libsource (lib "eagle-import") (part "POT_USVERTICAL_PS"))
    )
    (comp (ref "R5")
      (value "100k")
      (footprint "eagle-import:R0603")
      (libsource (lib "eagle-import") (part "R-US_R0603"))
    )
    (comp (ref "R6")
      (value "100k")
      (footprint "eagle-import:R0603")
      (libsource (lib "eagle-import") (part "R-US_R0603"))
    )
    (comp (ref "R7")
      (value "100k")
      (footprint "eagle-import:R0603")
      (libsource (lib "eagle-import") (part "R-US_R0603"))
    )
    (comp (ref "R8")
      (value "100k")
      (footprint "eagle-import:R0603")
      (libsource (lib "eagle-import") (part "R-US_R0603"))
    )
    (comp (ref "R9")
      (value "100k")
      (footprint "eagle-import:R0603")
      (libsource (lib "eagle-import") (part "R-US_R0603"))
    )
    (comp (ref "R10")
      (value "100k")
      (footprint "eagle-import:R0603")
      (libsource (lib "eagle-import") (part "R-US_R0603"))
    )
    (comp (ref "R11")
      (value "100k")
      (footprint "eagle-import:R0603")
      (libsource (lib "eagle-import") (part "R-US_R0603"))
    )
    (comp (ref "R12")
      (value "100k")
      (footprint "eagle-import:R0603")
      (libsource (lib "eagle-import") (part "R-US_R0603"))
    )
    (comp (ref "R13")
      (value "18k")
      (footprint "eagle-import:R0603")
      (libsource (lib "eagle-import") (part "R-US_R0603"))
    )
    (comp (ref "R14")
      (value "18k")
      (footprint "eagle-import:R0603")
      (libsource (lib "eagle-import") (part "R-US_R0603"))
    )
    (comp (ref "R15")
      (value "100k")
      (footprint "eagle-import:R0603")
      (libsource (lib "eagle-import") (part "R-US_R0603"))
    )
    (comp (ref "R16")
      (value "100k")
      (footprint "eagle-import:R0603")
      (libsource (lib "eagle-import") (part "R-US_R0603"))
    )
    (comp (ref "R17")
      (value "100k")
      (footprint "eagle-import:R0603")
      (libsource (lib "eagle-import") (part "R-US_R0603"))
    )
    (comp (ref "R18")
      (value "100k")
      (footprint "eagle-import:R0603")
      (libsource (lib "eagle-import") (part "R-US_R0603"))
    )
    (comp (ref "R19")
      (value "100k")
      (footprint "eagle-import:R0603")
      (libsource (lib "eagle-import") (part "R-US_R0603"))
    )
    (comp (ref "R20")
      (value "510")
      (footprint "eagle-import:R0603")
      (libsource (lib "eagle-import") (part "R-US_R0603"))
    )
    (comp (ref "R21")
      (value "510")
      (footprint "eagle-import:R0603")
      (libsource (lib "eagle-import") (part "R-US_R0603"))
    )
    (comp (ref "R22")
      (value "12k")
      (footprint "eagle-import:R0603")
      (libsource (lib "eagle-import") (part "R-US_R0603"))
    )
    (comp (ref "R23")
      (value "12k")
      (footprint "eagle-import:R0603")
      (libsource (lib "eagle-import") (part "R-US_R0603"))
    )
    (comp (ref "R24")
      (value "510")
      (footprint "eagle-import:R0603")
      (libsource (lib "eagle-import") (part "R-US_R0603"))
    )
    (comp (ref "R25")
      (value "510")
      (footprint "eagle-import:R0603")
      (libsource (lib "eagle-import") (part "R-US_R0603"))
    )
    (comp (ref "R26")
      (value "120k")
      (footprint "eagle-import:R0603")
      (libsource (lib "eagle-import") (part "R-US_R0603"))
    )
    (comp (ref "R27")
      (value "120k")
      (footprint "eagle-import:R0603")
      (libsource (lib "eagle-import") (part "R-US_R0603"))
    )
    (comp (ref "R28")
      (value "200k")
      (footprint "eagle-import:R0603")
      (libsource (lib "eagle-import") (part "R-US_R0603"))
    )
    (comp (ref "R29")
      (value "200k")
      (footprint "eagle-import:R0603")
      (libsource (lib "eagle-import") (part "R-US_R0603"))
    )
    (comp (ref "R30")
      (value "120k")
      (footprint "eagle-import:R0603")
      (libsource (lib "eagle-import") (part "R-US_R0603"))
    )
    (comp (ref "R31")
      (value "120k")
      (footprint "eagle-import:R0603")
      (libsource (lib "eagle-import") (part "R-US_R0603"))
    )
    (comp (ref "R32")
      (value "100k")
      (footprint "eagle-import:R0603")
      (libsource (lib "eagle-import") (part "R-US_R0603"))
    )
    (comp (ref "R33")
      (value "100k")
      (footprint "eagle-import:R0603")
      (libsource (lib "eagle-import") (part "R-US_R0603"))
    )
    (comp (ref "R100")
      (value "10kB")
      (footprint "eagle-import:ALPS_POT_VERTICAL_PS")
      (libsource (lib "eagle-import") (part "POT_USVERTICAL_PS"))
    )
    (comp (ref "R101")
      (value "10kB")
      (footprint "eagle-import:ALPS_POT_VERTICAL_PS")
      (libsource (lib "eagle-import") (part "POT_USVERTICAL_PS"))
    )
    (comp (ref "R108")
      (value "100k")
      (footprint "eagle-import:R0603")
      (libsource (lib "eagle-import") (part "R-US_R0603"))
    )
    (comp (ref "R109")
      (value "100k")
      (footprint "eagle-import:R0603")
      (libsource (lib "eagle-import") (part "R-US_R0603"))
    )
    (comp (ref "C1")
      (value "22u")
      (footprint "eagle-import:PANASONIC_C")
      (libsource (lib "eagle-import") (part "CPOL-USC"))
    )
    (comp (ref "C2")
      (value "22u")
      (footprint "eagle-import:PANASONIC_C")
      (libsource (lib "eagle-import") (part "CPOL-USC"))
    )
    (comp (ref "C3")
      (value "100n")
      (footprint "eagle-import:C0603")
      (libsource (lib "eagle-import") (part "C-USC0603"))
    )
    (comp (ref "C4")
      (value "100n")
      (footprint "eagle-import:C0603")
      (libsource (lib "eagle-import") (part "C-USC0603"))
    )
    (comp (ref "D1")
      (value "1N5819HW")
      (footprint "eagle-import:SOD123")
      (libsource (lib "eagle-import") (part "DIODE-SOD123"))
    )
    (comp (ref "D2")
      (value "1N5819HW")
      (footprint "eagle-import:SOD123")
      (libsource (lib "eagle-import") (part "DIODE-SOD123"))
    )
    (comp (ref "IC1")
      (value "LM4040B10")
      (footprint "eagle-import:DBZ_R-PDSO-G3")
      (libsource (lib "eagle-import") (part "LM4041DBZB12"))
    )
    (comp (ref "IC2")
      (value "LM4040B10")
      (footprint "eagle-import:DBZ_R-PDSO-G3")
      (libsource (lib "eagle-import") (part "LM4041DBZB12"))
    )
    (comp (ref "JP1")
      (value "FIDUCIAL1X2")
      (footprint "eagle-import:FIDUCIAL-1X2")
      (libsource (lib "eagle-import") (part "FIDUCIAL1X2"))
    )
    (comp (ref "JP2")
      (value "FIDUCIAL1X2")
      (footprint "eagle-import:FIDUCIAL-1X2")
      (libsource (lib "eagle-import") (part "FIDUCIAL1X2"))
    )
    (comp (ref "JP3")
      (value "FIDUCIAL1X2")
      (footprint "eagle-import:FIDUCIAL-1X2")
      (libsource (lib "eagle-import") (part "FIDUCIAL1X2"))
    )
    (comp (ref "JP4")
      (value "FIDUCIAL1X2")
      (footprint "eagle-import:FIDUCIAL-1X2")
      (libsource (lib "eagle-import") (part "FIDUCIAL1X2"))
    )
    (comp (ref "JP11")
      (value "M05X2PTH")
      (footprint "eagle-import:AVR_ICSP")
      (libsource (lib "eagle-import") (part "M05X2PTH"))
    )
    (comp (ref "P1")
      (value "PTCSMD")
      (footprint "eagle-import:PTC-1206")
      (libsource (lib "eagle-import") (part "PTCSMD"))
    )
    (comp (ref "R1")
      (value "3.3k")
      (footprint "eagle-import:R0603")
      (libsource (lib "eagle-import") (part "R-US_R0603"))
    )
    (comp (ref "R2")
      (value "1.0k")
      (footprint "eagle-import:R0603")
      (libsource (lib "eagle-import") (part "R-US_R0603"))
    )
    (comp (ref "C36")
      (value "100n")
      (footprint "eagle-import:C0603")
      (libsource (lib "eagle-import") (part "C-USC0603"))
    )
    (comp (ref "C37")
      (value "100n")
      (footprint "eagle-import:C0603")
      (libsource (lib "eagle-import") (part "C-USC0603"))
    )
    (comp (ref "C38")
      (value "560p")
      (footprint "eagle-import:C0603")
      (libsource (lib "eagle-import") (part "C-USC0603"))
    )
    (comp (ref "C39")
      (value "560p")
      (footprint "eagle-import:C0603")
      (libsource (lib "eagle-import") (part "C-USC0603"))
    )
    (comp (ref "C40")
      (value "68p")
      (footprint "eagle-import:C0603")
      (libsource (lib "eagle-import") (part "C-USC0603"))
    )
    (comp (ref "C41")
      (value "68p")
      (footprint "eagle-import:C0603")
      (libsource (lib "eagle-import") (part "C-USC0603"))
    )
    (comp (ref "C42")
      (value "100n")
      (footprint "eagle-import:C0603")
      (libsource (lib "eagle-import") (part "C-USC0603"))
    )
    (comp (ref "C43")
      (value "100n")
      (footprint "eagle-import:C0603")
      (libsource (lib "eagle-import") (part "C-USC0603"))
    )
    (comp (ref "C44")
      (value "100n")
      (footprint "eagle-import:C0603")
      (libsource (lib "eagle-import") (part "C-USC0603"))
    )
    (comp (ref "C45")
      (value "560p")
      (footprint "eagle-import:C0603")
      (libsource (lib "eagle-import") (part "C-USC0603"))
    )
    (comp (ref "C46")
      (value "560p")
      (footprint "eagle-import:C0603")
      (libsource (lib "eagle-import") (part "C-USC0603"))
    )
    (comp (ref "C47")
      (value "560p")
      (footprint "eagle-import:C0603")
      (libsource (lib "eagle-import") (part "C-USC0603"))
    )
    (comp (ref "C48")
      (value "560p")
      (footprint "eagle-import:C0603")
      (libsource (lib "eagle-import") (part "C-USC0603"))
    )
    (comp (ref "C49")
      (value "560p")
      (footprint "eagle-import:C0603")
      (libsource (lib "eagle-import") (part "C-USC0603"))
    )
    (comp (ref "C51")
      (value "100n")
      (footprint "eagle-import:C0603")
      (libsource (lib "eagle-import") (part "C-USC0603"))
    )
    (comp (ref "D10")
      (value "1N4148")
      (footprint "eagle-import:SOD323-W")
      (libsource (lib "eagle-import") (part "DIODE-SOD323-W"))
    )
    (comp (ref "D11")
      (value "1N4148")
      (footprint "eagle-import:SOD323-W")
      (libsource (lib "eagle-import") (part "DIODE-SOD323-W"))
    )
    (comp (ref "D12")
      (value "1N4148")
      (footprint "eagle-import:SOD323-W")
      (libsource (lib "eagle-import") (part "DIODE-SOD323-W"))
    )
    (comp (ref "D16")
      (value "1N4148")
      (footprint "eagle-import:SOD323-W")
      (libsource (lib "eagle-import") (part "DIODE-SOD323-W"))
    )
    (comp (ref "IC9")
      (value "TL074D")
      (footprint "eagle-import:SO14")
      (libsource (lib "eagle-import") (part "TL074D"))
    )
    (comp (ref "IC10")
      (value "TL074D")
      (footprint "eagle-import:SO14")
      (libsource (lib "eagle-import") (part "TL074D"))
    )
    (comp (ref "IC11")
      (value "V2164SZ")
      (footprint "eagle-import:SOIC16N")
      (libsource (lib "eagle-import") (part "SSM2164S"))
    )
    (comp (ref "J6")
      (value "PJ301_THONKICONN6")
      (footprint "eagle-import:WQP_PJ_301M6")
      (libsource (lib "eagle-import") (part "PJ301_THONKICONN6"))
    )
    (comp (ref "J7")
      (value "PJ301_THONKICONN6")
      (footprint "eagle-import:WQP_PJ_301M6")
      (libsource (lib "eagle-import") (part "PJ301_THONKICONN6"))
    )
    (comp (ref "J8")
      (value "PJ301_THONKICONN6")
      (footprint "eagle-import:WQP_PJ_301M6")
      (libsource (lib "eagle-import") (part "PJ301_THONKICONN6"))
    )
    (comp (ref "JP6")
      (value "M03PTH")
      (footprint "eagle-import:1X03")
      (libsource (lib "eagle-import") (part "M03PTH"))
    )
    (comp (ref "JP13")
      (value "M03PTH")
      (footprint "eagle-import:1X03")
      (libsource (lib "eagle-import") (part "M03PTH"))
    )
    (comp (ref "R65")
      (value "10kB")
      (footprint "eagle-import:ALPS_POT_VERTICAL")
      (libsource (lib "eagle-import") (part "POT_USVERTICAL"))
    )
    (comp (ref "R68")
      (value "10kB")
      (footprint "eagle-import:ALPS_POT_VERTICAL_PS")
      (libsource (lib "eagle-import") (part "POT_USVERTICAL_PS"))
    )
    (comp (ref "R69")
      (value "10kB")
      (footprint "eagle-import:ALPS_POT_VERTICAL_PS")
      (libsource (lib "eagle-import") (part "POT_USVERTICAL_PS"))
    )
    (comp (ref "R70")
      (value "200k")
      (footprint "eagle-import:R0603")
      (libsource (lib "eagle-import") (part "R-US_R0603"))
    )
    (comp (ref "R71")
      (value "100k")
      (footprint "eagle-import:R0603")
      (libsource (lib "eagle-import") (part "R-US_R0603"))
    )
    (comp (ref "R72")
      (value "100k")
      (footprint "eagle-import:R0603")
      (libsource (lib "eagle-import") (part "R-US_R0603"))
    )
    (comp (ref "R73")
      (value "100k")
      (footprint "eagle-import:R0603")
      (libsource (lib "eagle-import") (part "R-US_R0603"))
    )
    (comp (ref "R74")
      (value "100k")
      (footprint "eagle-import:R0603")
      (libsource (lib "eagle-import") (part "R-US_R0603"))
    )
    (comp (ref "R75")
      (value "100k")
      (footprint "eagle-import:R0603")
      (libsource (lib "eagle-import") (part "R-US_R0603"))
    )
    (comp (ref "R76")
      (value "100k")
      (footprint "eagle-import:R0603")
      (libsource (lib "eagle-import") (part "R-US_R0603"))
    )
    (comp (ref "R77")
      (value "100k")
      (footprint "eagle-import:R0603")
      (libsource (lib "eagle-import") (part "R-US_R0603"))
    )
    (comp (ref "R78")
      (value "120k")
      (footprint "eagle-import:R0603")
      (libsource (lib "eagle-import") (part "R-US_R0603"))
    )
    (comp (ref "R79")
      (value "120k")
      (footprint "eagle-import:R0603")
      (libsource (lib "eagle-import") (part "R-US_R0603"))
    )
    (comp (ref "R80")
      (value "200k")
      (footprint "eagle-import:R0603")
      (libsource (lib "eagle-import") (part "R-US_R0603"))
    )
    (comp (ref "R81")
      (value "100k")
      (footprint "eagle-import:R0603")
      (libsource (lib "eagle-import") (part "R-US_R0603"))
    )
    (comp (ref "R82")
      (value "100k")
      (footprint "eagle-import:R0603")
      (libsource (lib "eagle-import") (part "R-US_R0603"))
    )
    (comp (ref "R83")
      (value "100k")
      (footprint "eagle-import:R0603")
      (libsource (lib "eagle-import") (part "R-US_R0603"))
    )
    (comp (ref "R84")
      (value "12k")
      (footprint "eagle-import:R0603")
      (libsource (lib "eagle-import") (part "R-US_R0603"))
    )
    (comp (ref "R85")
      (value "18k")
      (footprint "eagle-import:R0603")
      (libsource (lib "eagle-import") (part "R-US_R0603"))
    )
    (comp (ref "R86")
      (value "100k")
      (footprint "eagle-import:R0603")
      (libsource (lib "eagle-import") (part "R-US_R0603"))
    )
    (comp (ref "R87")
      (value "100k")
      (footprint "eagle-import:R0603")
      (libsource (lib "eagle-import") (part "R-US_R0603"))
    )
    (comp (ref "R88")
      (value "100k")
      (footprint "eagle-import:R0603")
      (libsource (lib "eagle-import") (part "R-US_R0603"))
    )
    (comp (ref "R89")
      (value "510")
      (footprint "eagle-import:R0603")
      (libsource (lib "eagle-import") (part "R-US_R0603"))
    )
    (comp (ref "R90")
      (value "510")
      (footprint "eagle-import:R0603")
      (libsource (lib "eagle-import") (part "R-US_R0603"))
    )
    (comp (ref "R91")
      (value "100k")
      (footprint "eagle-import:R0603")
      (libsource (lib "eagle-import") (part "R-US_R0603"))
    )
    (comp (ref "R92")
      (value "100k")
      (footprint "eagle-import:R0603")
      (libsource (lib "eagle-import") (part "R-US_R0603"))
    )
    (comp (ref "R93")
      (value "22k")
      (footprint "eagle-import:R0603")
      (libsource (lib "eagle-import") (part "R-US_R0603"))
    )
    (comp (ref "R94")
      (value "510")
      (footprint "eagle-import:R0603")
      (libsource (lib "eagle-import") (part "R-US_R0603"))
    )
    (comp (ref "R95")
      (value "150k")
      (footprint "eagle-import:R0603")
      (libsource (lib "eagle-import") (part "R-US_R0603"))
    )
    (comp (ref "R96")
      (value "1.5M")
      (footprint "eagle-import:R0603")
      (libsource (lib "eagle-import") (part "R-US_R0603"))
    )
    (comp (ref "R97")
      (value "510")
      (footprint "eagle-import:R0603")
      (libsource (lib "eagle-import") (part "R-US_R0603"))
    )
    (comp (ref "R98")
      (value "100k")
      (footprint "eagle-import:R0603")
      (libsource (lib "eagle-import") (part "R-US_R0603"))
    )
    (comp (ref "R99")
      (value "100k")
      (footprint "eagle-import:R0603")
      (libsource (lib "eagle-import") (part "R-US_R0603"))
    )
  )
  (nets
    (net (code "1") (name "AREF_+10") (class "Default")
      (node (ref "C3") (pin "1") (pinfunction "1_1") (pintype "passive"))
      (node (ref "IC1") (pin "1") (pinfunction "C_1") (pintype "passive"))
      (node (ref "R1") (pin "2") (pinfunction "2_2") (pintype "passive"))
      (node (ref "R118") (pin "2") (pinfunction "2_2") (pintype "passive"))
      (node (ref "R121") (pin "2") (pinfunction "2_2") (pintype "passive"))
      (node (ref "R28") (pin "1") (pinfunction "1_1") (pintype "passive"))
      (node (ref "R29") (pin "1") (pinfunction "1_1") (pintype "passive"))
      (node (ref "R46") (pin "1") (pinfunction "1_1") (pintype "passive"))
      (node (ref "R63") (pin "1") (pinfunction "1_1") (pintype "passive"))
      (node (ref "R80") (pin "1") (pinfunction "1_1") (pintype "passive"))
      (node (ref "R96") (pin "1") (pinfunction "1_1") (pintype "passive"))
    )
    (net (code "2") (name "AREF_-10") (class "Default")
      (node (ref "C4") (pin "1") (pinfunction "1_1") (pintype "passive"))
      (node (ref "IC2") (pin "2") (pinfunction "A_2") (pintype "passive"))
      (node (ref "R108") (pin "1") (pinfunction "1_1") (pintype "passive"))
      (node (ref "R109") (pin "1") (pinfunction "1_1") (pintype "passive"))
      (node (ref "R12") (pin "1") (pinfunction "1_1") (pintype "passive"))
      (node (ref "R2") (pin "2") (pinfunction "2_2") (pintype "passive"))
      (node (ref "R43") (pin "1") (pinfunction "1_1") (pintype "passive"))
      (node (ref "R49") (pin "1") (pinfunction "1_1") (pintype "passive"))
      (node (ref "R5") (pin "1") (pinfunction "1_1") (pintype "passive"))
      (node (ref "R54") (pin "1") (pinfunction "1_1") (pintype "passive"))
      (node (ref "R70") (pin "1") (pinfunction "1_1") (pintype "passive"))
      (node (ref "R77") (pin "1") (pinfunction "1_1") (pintype "passive"))
      (node (ref "R83") (pin "1") (pinfunction "1_1") (pintype "passive"))
    )
    (net (code "3") (name "BP_1") (class "Default")
      (node (ref "C40") (pin "2") (pinfunction "2_2") (pintype "passive"))
      (node (ref "IC9") (pin "7") (pinfunction "OUT_7") (pintype "output"))
      (node (ref "JP13") (pin "1") (pinfunction "1_1") (pintype "passive"))
      (node (ref "R87") (pin "1") (pinfunction "1_1") (pintype "passive"))
      (node (ref "R98") (pin "1") (pinfunction "1_1") (pintype "passive"))
    )
    (net (code "4") (name "BP_2") (class "Default")
      (node (ref "C25") (pin "2") (pinfunction "2_2") (pintype "passive"))
      (node (ref "IC6") (pin "7") (pinfunction "OUT_7") (pintype "output"))
      (node (ref "JP5") (pin "1") (pinfunction "1_1") (pintype "passive"))
      (node (ref "R53") (pin "1") (pinfunction "1_1") (pintype "passive"))
      (node (ref "R66") (pin "1") (pinfunction "1_1") (pintype "passive"))
    )
    (net (code "5") (name "F_GLOBAL") (class "Default")
      (node (ref "J11") (pin "P3") (pinfunction "3_P3") (pintype "passive"))
      (node (ref "R47") (pin "1") (pinfunction "1_1") (pintype "passive"))
      (node (ref "R7") (pin "1") (pinfunction "1_1") (pintype "passive"))
      (node (ref "R8") (pin "1") (pinfunction "1_1") (pintype "passive"))
      (node (ref "R81") (pin "1") (pinfunction "1_1") (pintype "passive"))
    )
    (net (code "6") (name "GAIN_GLOBAL") (class "Default")
      (node (ref "J12") (pin "P3") (pinfunction "3_P3") (pintype "passive"))
      (node (ref "R26") (pin "1") (pinfunction "1_1") (pintype "passive"))
      (node (ref "R31") (pin "1") (pinfunction "1_1") (pintype "passive"))
      (node (ref "R44") (pin "1") (pinfunction "1_1") (pintype "passive"))
      (node (ref "R79") (pin "1") (pinfunction "1_1") (pintype "passive"))
    )
    (net (code "7") (name "GND") (class "Default")
      (node (ref "C1") (pin "-") (pinfunction "-_-") (pintype "passive"))
      (node (ref "C12") (pin "2") (pinfunction "2_2") (pintype "passive"))
      (node (ref "C13") (pin "1") (pinfunction "1_1") (pintype "passive"))
      (node (ref "C14") (pin "2") (pinfunction "2_2") (pintype "passive"))
      (node (ref "C15") (pin "2") (pinfunction "2_2") (pintype "passive"))
      (node (ref "C18") (pin "2") (pinfunction "2_2") (pintype "passive"))
      (node (ref "C19") (pin "2") (pinfunction "2_2") (pintype "passive"))
      (node (ref "C2") (pin "+") (pinfunction "+_+") (pintype "passive"))
      (node (ref "C20") (pin "1") (pinfunction "1_1") (pintype "passive"))
      (node (ref "C21") (pin "2") (pinfunction "2_2") (pintype "passive"))
      (node (ref "C22") (pin "1") (pinfunction "1_1") (pintype "passive"))
      (node (ref "C27") (pin "2") (pinfunction "2_2") (pintype "passive"))
      (node (ref "C28") (pin "1") (pinfunction "1_1") (pintype "passive"))
      (node (ref "C29") (pin "2") (pinfunction "2_2") (pintype "passive"))
      (node (ref "C3") (pin "2") (pinfunction "2_2") (pintype "passive"))
      (node (ref "C30") (pin "2") (pinfunction "2_2") (pintype "passive"))
      (node (ref "C31") (pin "2") (pinfunction "2_2") (pintype "passive"))
      (node (ref "C33") (pin "2") (pinfunction "2_2") (pintype "passive"))
      (node (ref "C34") (pin "2") (pinfunction "2_2") (pintype "passive"))
      (node (ref "C35") (pin "1") (pinfunction "1_1") (pintype "passive"))
      (node (ref "C36") (pin "2") (pinfunction "2_2") (pintype "passive"))
      (node (ref "C37") (pin "1") (pinfunction "1_1") (pintype "passive"))
      (node (ref "C4") (pin "2") (pinfunction "2_2") (pintype "passive"))
      (node (ref "C42") (pin "2") (pinfunction "2_2") (pintype "passive"))
      (node (ref "C43") (pin "2") (pinfunction "2_2") (pintype "passive"))
      (node (ref "C44") (pin "1") (pinfunction "1_1") (pintype "passive"))
      (node (ref "C45") (pin "2") (pinfunction "2_2") (pintype "passive"))
      (node (ref "C47") (pin "2") (pinfunction "2_2") (pintype "passive"))
      (node (ref "C48") (pin "2") (pinfunction "2_2") (pintype "passive"))
      (node (ref "C49") (pin "2") (pinfunction "2_2") (pintype "passive"))
      (node (ref "C5") (pin "2") (pinfunction "2_2") (pintype "passive"))
      (node (ref "C50") (pin "2") (pinfunction "2_2") (pintype "passive"))
      (node (ref "C51") (pin "1") (pinfunction "1_1") (pintype "passive"))
      (node (ref "C52") (pin "2") (pinfunction "2_2") (pintype "passive"))
      (node (ref "C53") (pin "1") (pinfunction "1_1") (pintype "passive"))
      (node (ref "C54") (pin "1") (pinfunction "1_1") (pintype "passive"))
      (node (ref "C55") (pin "2") (pinfunction "2_2") (pintype "passive"))
      (node (ref "C56") (pin "2") (pinfunction "2_2") (pintype "passive"))
      (node (ref "C58") (pin "-") (pinfunction "-_-") (pintype "passive"))
      (node (ref "C8") (pin "1") (pinfunction "1_1") (pintype "passive"))
      (node (ref "C9") (pin "2") (pinfunction "2_2") (pintype "passive"))
      (node (ref "D1") (pin "C") (pinfunction "C_C") (pintype "passive"))
      (node (ref "D10") (pin "A") (pinfunction "A_A") (pintype "passive"))
      (node (ref "D12") (pin "A") (pinfunction "A_A") (pintype "passive"))
      (node (ref "D3") (pin "A") (pinfunction "A_A") (pintype "passive"))
      (node (ref "D4") (pin "A") (pinfunction "A_A") (pintype "passive"))
      (node (ref "D5") (pin "A") (pinfunction "A_A") (pintype "passive"))
      (node (ref "D6") (pin "A") (pinfunction "A_A") (pintype "passive"))
      (node (ref "D7") (pin "A") (pinfunction "A_A") (pintype "passive"))
      (node (ref "D9") (pin "A") (pinfunction "A_A") (pintype "passive"))
      (node (ref "IC1") (pin "2") (pinfunction "A_2") (pintype "passive"))
      (node (ref "IC10") (pin "10") (pinfunction "+IN_10") (pintype "input"))
      (node (ref "IC10") (pin "12") (pinfunction "+IN_12") (pintype "input"))
      (node (ref "IC10") (pin "3") (pinfunction "+IN_3") (pintype "input"))
      (node (ref "IC10") (pin "5") (pinfunction "+IN_5") (pintype "input"))
      (node (ref "IC11") (pin "8") (pinfunction "GND_8") (pintype "power_in"))
      (node (ref "IC12") (pin "3") (pinfunction "+IN_3") (pintype "input"))
      (node (ref "IC12") (pin "5") (pinfunction "+IN_5") (pintype "input"))
      (node (ref "IC13") (pin "3") (pinfunction "+IN_3") (pintype "input"))
      (node (ref "IC13") (pin "5") (pinfunction "+IN_5") (pintype "input"))
      (node (ref "IC14") (pin "4") (pinfunction "V-_4") (pintype "power_in"))
      (node (ref "IC2") (pin "1") (pinfunction "C_1") (pintype "passive"))
      (node (ref "IC3") (pin "3") (pinfunction "+IN_3") (pintype "input"))
      (node (ref "IC3") (pin "5") (pinfunction "+IN_5") (pintype "input"))
      (node (ref "IC4") (pin "10") (pinfunction "+IN_10") (pintype "input"))
      (node (ref "IC4") (pin "12") (pinfunction "+IN_12") (pintype "input"))
      (node (ref "IC4") (pin "3") (pinfunction "+IN_3") (pintype "input"))
      (node (ref "IC4") (pin "5") (pinfunction "+IN_5") (pintype "input"))
      (node (ref "IC5") (pin "8") (pinfunction "GND_8") (pintype "power_in"))
      (node (ref "IC6") (pin "10") (pinfunction "+IN_10") (pintype "input"))
      (node (ref "IC6") (pin "12") (pinfunction "+IN_12") (pintype "input"))
      (node (ref "IC6") (pin "3") (pinfunction "+IN_3") (pintype "input"))
      (node (ref "IC6") (pin "5") (pinfunction "+IN_5") (pintype "input"))
      (node (ref "IC7") (pin "10") (pinfunction "+IN_10") (pintype "input"))
      (node (ref "IC7") (pin "12") (pinfunction "+IN_12") (pintype "input"))
      (node (ref "IC7") (pin "3") (pinfunction "+IN_3") (pintype "input"))
      (node (ref "IC7") (pin "5") (pinfunction "+IN_5") (pintype "input"))
      (node (ref "IC8") (pin "8") (pinfunction "GND_8") (pintype "power_in"))
      (node (ref "IC9") (pin "10") (pinfunction "+IN_10") (pintype "input"))
      (node (ref "IC9") (pin "12") (pinfunction "+IN_12") (pintype "input"))
      (node (ref "IC9") (pin "3") (pinfunction "+IN_3") (pintype "input"))
      (node (ref "IC9") (pin "5") (pinfunction "+IN_5") (pintype "input"))
      (node (ref "J1") (pin "P1") (pinfunction "1_P1") (pintype "passive"))
      (node (ref "J10") (pin "P1") (pinfunction "1_P1") (pintype "passive"))
      (node (ref "J11") (pin "P1") (pinfunction "1_P1") (pintype "passive"))
      (node (ref "J12") (pin "P1") (pinfunction "1_P1") (pintype "passive"))
      (node (ref "J13") (pin "P1") (pinfunction "1_P1") (pintype "passive"))
      (node (ref "J14") (pin "P1") (pinfunction "1_P1") (pintype "passive"))
      (node (ref "J2") (pin "P1") (pinfunction "1_P1") (pintype "passive"))
      (node (ref "J3") (pin "P1") (pinfunction "1_P1") (pintype "passive"))
      (node (ref "J4") (pin "P1") (pinfunction "1_P1") (pintype "passive"))
      (node (ref "J5") (pin "P1") (pinfunction "1_P1") (pintype "passive"))
      (node (ref "J6") (pin "P1") (pinfunction "1_P1") (pintype "passive"))
      (node (ref "J7") (pin "P1") (pinfunction "1_P1") (pintype "passive"))
      (node (ref "J8") (pin "P1") (pinfunction "1_P1") (pintype "passive"))
      (node (ref "J9") (pin "P1") (pinfunction "1_P1") (pintype "passive"))
      (node (ref "JP11") (pin "3") (pinfunction "3_3") (pintype "passive"))
      (node (ref "JP11") (pin "4") (pinfunction "4_4") (pintype "passive"))
      (node (ref "JP11") (pin "5") (pinfunction "5_5") (pintype "passive"))
      (node (ref "JP11") (pin "6") (pinfunction "6_6") (pintype "passive"))
      (node (ref "JP11") (pin "7") (pinfunction "7_7") (pintype "passive"))
      (node (ref "JP11") (pin "8") (pinfunction "8_8") (pintype "passive"))
      (node (ref "JP6") (pin "1") (pinfunction "1_1") (pintype "passive"))
      (node (ref "JP6") (pin "2") (pinfunction "2_2") (pintype "passive"))
      (node (ref "JP6") (pin "3") (pinfunction "3_3") (pintype "passive"))
      (node (ref "JP7") (pin "1") (pinfunction "1_1") (pintype "passive"))
      (node (ref "JP7") (pin "2") (pinfunction "2_2") (pintype "passive"))
      (node (ref "JP7") (pin "3") (pinfunction "3_3") (pintype "passive"))
      (node (ref "Q1") (pin "E") (pinfunction "E_E") (pintype "passive"))
      (node (ref "R100") (pin "P$1") (pinfunction "E_P$1") (pintype "passive"))
      (node (ref "R101") (pin "P$1") (pinfunction "E_P$1") (pintype "passive"))
      (node (ref "R116") (pin "1") (pinfunction "1_1") (pintype "passive"))
      (node (ref "R117") (pin "1") (pinfunction "1_1") (pintype "passive"))
      (node (ref "R120") (pin "1") (pinfunction "1_1") (pintype "passive"))
      (node (ref "R3") (pin "P$1") (pinfunction "E_P$1") (pintype "passive"))
      (node (ref "R34") (pin "P$1") (pinfunction "E_P$1") (pintype "passive"))
      (node (ref "R36") (pin "P$1") (pinfunction "E_P$1") (pintype "passive"))
      (node (ref "R4") (pin "P$1") (pinfunction "E_P$1") (pintype "passive"))
      (node (ref "R42") (pin "P$3") (pinfunction "A_P$3") (pintype "passive"))
      (node (ref "R65") (pin "P$3") (pinfunction "A_P$3") (pintype "passive"))
      (node (ref "R68") (pin "P$1") (pinfunction "E_P$1") (pintype "passive"))
      (node (ref "R69") (pin "P$1") (pinfunction "E_P$1") (pintype "passive"))
    )
    (net (code "8") (name "HP_1") (class "Default")
      (node (ref "IC9") (pin "1") (pinfunction "OUT_1") (pintype "output"))
      (node (ref "JP13") (pin "3") (pinfunction "3_3") (pintype "passive"))
      (node (ref "R75") (pin "2") (pinfunction "2_2") (pintype "passive"))
      (node (ref "R86") (pin "1") (pinfunction "1_1") (pintype "passive"))
    )
    (net (code "9") (name "HP_2") (class "Default")
      (node (ref "IC6") (pin "1") (pinfunction "OUT_1") (pintype "output"))
      (node (ref "JP5") (pin "3") (pinfunction "3_3") (pintype "passive"))
      (node (ref "R40") (pin "2") (pinfunction "2_2") (pintype "passive"))
      (node (ref "R52") (pin "1") (pinfunction "1_1") (pintype "passive"))
    )
    (net (code "10") (name "IN") (class "Default")
      (node (ref "IC12") (pin "7") (pinfunction "OUT_7") (pintype "output"))
      (node (ref "JP12") (pin "3") (pinfunction "3_3") (pintype "passive"))
      (node (ref "R103") (pin "2") (pinfunction "2_2") (pintype "passive"))
      (node (ref "R15") (pin "1") (pinfunction "1_1") (pintype "passive"))
      (node (ref "R16") (pin "1") (pinfunction "1_1") (pintype "passive"))
      (node (ref "R17") (pin "1") (pinfunction "1_1") (pintype "passive"))
      (node (ref "R37") (pin "1") (pinfunction "1_1") (pintype "passive"))
      (node (ref "R72") (pin "1") (pinfunction "1_1") (pintype "passive"))
    )
    (net (code "11") (name "MINUS_BUS") (class "Default")
      (node (ref "IC11") (pin "12") (pinfunction "OUT_12") (pintype "output"))
      (node (ref "IC13") (pin "2") (pinfunction "-IN_2") (pintype "input"))
      (node (ref "IC5") (pin "5") (pinfunction "OUT_5") (pintype "output"))
      (node (ref "IC8") (pin "12") (pinfunction "OUT_12") (pintype "output"))
      (node (ref "R104") (pin "2") (pinfunction "2_2") (pintype "passive"))
      (node (ref "R107") (pin "1") (pinfunction "1_1") (pintype "passive"))
      (node (ref "R19") (pin "2") (pinfunction "2_2") (pintype "passive"))
    )
    (net (code "12") (name "Net-(C14-Pad1)") (class "Default")
      (node (ref "C14") (pin "1") (pinfunction "1_1") (pintype "passive"))
      (node (ref "R21") (pin "1") (pinfunction "1_1") (pintype "passive"))
    )
    (net (code "13") (name "Net-(C15-Pad1)") (class "Default")
      (node (ref "C15") (pin "1") (pinfunction "1_1") (pintype "passive"))
      (node (ref "R20") (pin "1") (pinfunction "1_1") (pintype "passive"))
    )
    (net (code "14") (name "Net-(C18-Pad1)") (class "Default")
      (node (ref "C18") (pin "1") (pinfunction "1_1") (pintype "passive"))
      (node (ref "R24") (pin "1") (pinfunction "1_1") (pintype "passive"))
    )
    (net (code "15") (name "Net-(C19-Pad1)") (class "Default")
      (node (ref "C19") (pin "1") (pinfunction "1_1") (pintype "passive"))
      (node (ref "R25") (pin "1") (pinfunction "1_1") (pintype "passive"))
    )
    (net (code "16") (name "Net-(C29-Pad1)") (class "Default")
      (node (ref "C29") (pin "1") (pinfunction "1_1") (pintype "passive"))
      (node (ref "R56") (pin "1") (pinfunction "1_1") (pintype "passive"))
    )
    (net (code "17") (name "Net-(C30-Pad1)") (class "Default")
      (node (ref "C30") (pin "1") (pinfunction "1_1") (pintype "passive"))
      (node (ref "R57") (pin "1") (pinfunction "1_1") (pintype "passive"))
    )
    (net (code "18") (name "Net-(C33-Pad1)") (class "Default")
      (node (ref "C33") (pin "1") (pinfunction "1_1") (pintype "passive"))
      (node (ref "R61") (pin "1") (pinfunction "1_1") (pintype "passive"))
    )
    (net (code "19") (name "Net-(C34-Pad1)") (class "Default")
      (node (ref "C34") (pin "1") (pinfunction "1_1") (pintype "passive"))
      (node (ref "R64") (pin "1") (pinfunction "1_1") (pintype "passive"))
    )
    (net (code "20") (name "Net-(C45-Pad1)") (class "Default")
      (node (ref "C45") (pin "1") (pinfunction "1_1") (pintype "passive"))
      (node (ref "R89") (pin "1") (pinfunction "1_1") (pintype "passive"))
    )
    (net (code "21") (name "Net-(C47-Pad1)") (class "Default")
      (node (ref "C47") (pin "1") (pinfunction "1_1") (pintype "passive"))
      (node (ref "R90") (pin "1") (pinfunction "1_1") (pintype "passive"))
    )
    (net (code "22") (name "Net-(C48-Pad1)") (class "Default")
      (node (ref "C48") (pin "1") (pinfunction "1_1") (pintype "passive"))
      (node (ref "R94") (pin "1") (pinfunction "1_1") (pintype "passive"))
    )
    (net (code "23") (name "Net-(C49-Pad1)") (class "Default")
      (node (ref "C49") (pin "1") (pinfunction "1_1") (pintype "passive"))
      (node (ref "R97") (pin "1") (pinfunction "1_1") (pintype "passive"))
    )
    (net (code "24") (name "Net-(C55-Pad1)") (class "Default")
      (node (ref "C55") (pin "1") (pinfunction "1_1") (pintype "passive"))
      (node (ref "R113") (pin "2") (pinfunction "2_2") (pintype "passive"))
      (node (ref "R114") (pin "1") (pinfunction "1_1") (pintype "passive"))
    )
    (net (code "25") (name "Net-(C57-Pad1)") (class "Default")
      (node (ref "C57") (pin "1") (pinfunction "1_1") (pintype "passive"))
      (node (ref "R115") (pin "1") (pinfunction "1_1") (pintype "passive"))
    )
    (net (code "26") (name "Net-(D2-PadA)") (class "Default")
      (node (ref "D2") (pin "A") (pinfunction "A_A") (pintype "passive"))
      (node (ref "JP11") (pin "1") (pinfunction "1_1") (pintype "passive"))
      (node (ref "JP11") (pin "2") (pinfunction "2_2") (pintype "passive"))
    )
    (net (code "27") (name "Net-(D13-PadC)") (class "Default")
      (node (ref "D13") (pin "C") (pinfunction "C_C") (pintype "passive"))
      (node (ref "D14") (pin "C") (pinfunction "C_C") (pintype "passive"))
      (node (ref "R113") (pin "1") (pinfunction "1_1") (pintype "passive"))
    )
    (net (code "28") (name "Net-(IC3A--IN)") (class "Default")
      (node (ref "C6") (pin "1") (pinfunction "1_1") (pintype "passive"))
      (node (ref "IC3") (pin "2") (pinfunction "-IN_2") (pintype "input"))
      (node (ref "IC5") (pin "4") (pinfunction "OUT_4") (pintype "output"))
    )
    (net (code "29") (name "Net-(IC3A-OUT)") (class "Default")
      (node (ref "C6") (pin "2") (pinfunction "2_2") (pintype "passive"))
      (node (ref "IC3") (pin "1") (pinfunction "OUT_1") (pintype "output"))
      (node (ref "R11") (pin "2") (pinfunction "2_2") (pintype "passive"))
      (node (ref "R32") (pin "1") (pinfunction "1_1") (pintype "passive"))
      (node (ref "R33") (pin "1") (pinfunction "1_1") (pintype "passive"))
    )
    (net (code "30") (name "Net-(IC3B--IN)") (class "Default")
      (node (ref "C7") (pin "1") (pinfunction "1_1") (pintype "passive"))
      (node (ref "IC3") (pin "6") (pinfunction "-IN_6") (pintype "input"))
      (node (ref "IC5") (pin "13") (pinfunction "OUT_13") (pintype "output"))
    )
    (net (code "31") (name "Net-(IC3B-OUT)") (class "Default")
      (node (ref "C7") (pin "2") (pinfunction "2_2") (pintype "passive"))
      (node (ref "IC3") (pin "7") (pinfunction "OUT_7") (pintype "output"))
      (node (ref "R10") (pin "2") (pinfunction "2_2") (pintype "passive"))
      (node (ref "R18") (pin "1") (pinfunction "1_1") (pintype "passive"))
      (node (ref "R19") (pin "1") (pinfunction "1_1") (pintype "passive"))
    )
    (net (code "32") (name "Net-(IC4A--IN)") (class "Default")
      (node (ref "C10") (pin "2") (pinfunction "2_2") (pintype "passive"))
      (node (ref "IC4") (pin "2") (pinfunction "-IN_2") (pintype "input"))
      (node (ref "R13") (pin "1") (pinfunction "1_1") (pintype "passive"))
      (node (ref "R3") (pin "P$3") (pinfunction "A_P$3") (pintype "passive"))
      (node (ref "R6") (pin "2") (pinfunction "2_2") (pintype "passive"))
      (node (ref "R7") (pin "2") (pinfunction "2_2") (pintype "passive"))
    )
    (net (code "33") (name "Net-(IC4A-OUT)") (class "Default")
      (node (ref "C10") (pin "1") (pinfunction "1_1") (pintype "passive"))
      (node (ref "D3") (pin "C") (pinfunction "C_C") (pintype "passive"))
      (node (ref "IC4") (pin "1") (pinfunction "OUT_1") (pintype "output"))
      (node (ref "IC5") (pin "14") (pinfunction "CTRL_14") (pintype "input"))
      (node (ref "R13") (pin "2") (pinfunction "2_2") (pintype "passive"))
    )
    (net (code "34") (name "Net-(IC4B--IN)") (class "Default")
      (node (ref "C16") (pin "2") (pinfunction "2_2") (pintype "passive"))
      (node (ref "IC4") (pin "6") (pinfunction "-IN_6") (pintype "input"))
      (node (ref "R101") (pin "P$3") (pinfunction "A_P$3") (pintype "passive"))
      (node (ref "R22") (pin "1") (pinfunction "1_1") (pintype "passive"))
      (node (ref "R26") (pin "2") (pinfunction "2_2") (pintype "passive"))
      (node (ref "R27") (pin "2") (pinfunction "2_2") (pintype "passive"))
      (node (ref "R28") (pin "2") (pinfunction "2_2") (pintype "passive"))
    )
    (net (code "35") (name "Net-(IC4B-OUT)") (class "Default")
      (node (ref "C16") (pin "1") (pinfunction "1_1") (pintype "passive"))
      (node (ref "D6") (pin "C") (pinfunction "C_C") (pintype "passive"))
      (node (ref "IC4") (pin "7") (pinfunction "OUT_7") (pintype "output"))
      (node (ref "IC5") (pin "6") (pinfunction "CTRL_6") (pintype "input"))
      (node (ref "R22") (pin "2") (pinfunction "2_2") (pintype "passive"))
    )
    (net (code "36") (name "Net-(IC4C--IN)") (class "Default")
      (node (ref "C17") (pin "2") (pinfunction "2_2") (pintype "passive"))
      (node (ref "IC4") (pin "9") (pinfunction "-IN_9") (pintype "input"))
      (node (ref "R23") (pin "1") (pinfunction "1_1") (pintype "passive"))
      (node (ref "R29") (pin "2") (pinfunction "2_2") (pintype "passive"))
      (node (ref "R30") (pin "2") (pinfunction "2_2") (pintype "passive"))
      (node (ref "R31") (pin "2") (pinfunction "2_2") (pintype "passive"))
      (node (ref "R4") (pin "P$3") (pinfunction "A_P$3") (pintype "passive"))
    )
    (net (code "37") (name "Net-(IC4C-OUT)") (class "Default")
      (node (ref "C17") (pin "1") (pinfunction "1_1") (pintype "passive"))
      (node (ref "D5") (pin "C") (pinfunction "C_C") (pintype "passive"))
      (node (ref "IC4") (pin "8") (pinfunction "OUT_8") (pintype "output"))
      (node (ref "IC5") (pin "11") (pinfunction "CTRL_11") (pintype "input"))
      (node (ref "R23") (pin "2") (pinfunction "2_2") (pintype "passive"))
    )
    (net (code "38") (name "Net-(IC4D--IN)") (class "Default")
      (node (ref "C11") (pin "2") (pinfunction "2_2") (pintype "passive"))
      (node (ref "IC4") (pin "13") (pinfunction "-IN_13") (pintype "input"))
      (node (ref "R100") (pin "P$3") (pinfunction "A_P$3") (pintype "passive"))
      (node (ref "R14") (pin "1") (pinfunction "1_1") (pintype "passive"))
      (node (ref "R8") (pin "2") (pinfunction "2_2") (pintype "passive"))
      (node (ref "R9") (pin "2") (pinfunction "2_2") (pintype "passive"))
    )
    (net (code "39") (name "Net-(IC4D-OUT)") (class "Default")
      (node (ref "C11") (pin "1") (pinfunction "1_1") (pintype "passive"))
      (node (ref "D4") (pin "C") (pinfunction "C_C") (pintype "passive"))
      (node (ref "IC4") (pin "14") (pinfunction "OUT_14") (pintype "output"))
      (node (ref "IC5") (pin "3") (pinfunction "CTRL_3") (pintype "input"))
      (node (ref "R14") (pin "2") (pinfunction "2_2") (pintype "passive"))
    )
    (net (code "40") (name "Net-(IC5A-IN)") (class "Default")
      (node (ref "IC5") (pin "2") (pinfunction "IN_2") (pintype "input"))
      (node (ref "R11") (pin "1") (pinfunction "1_1") (pintype "passive"))
      (node (ref "R15") (pin "2") (pinfunction "2_2") (pintype "passive"))
      (node (ref "R20") (pin "2") (pinfunction "2_2") (pintype "passive"))
    )
    (net (code "41") (name "Net-(IC5B-IN)") (class "Default")
      (node (ref "IC5") (pin "7") (pinfunction "IN_7") (pintype "input"))
      (node (ref "R25") (pin "2") (pinfunction "2_2") (pintype "passive"))
      (node (ref "R32") (pin "2") (pinfunction "2_2") (pintype "passive"))
    )
    (net (code "42") (name "Net-(IC5C-IN)") (class "Default")
      (node (ref "IC5") (pin "10") (pinfunction "IN_10") (pintype "input"))
      (node (ref "R17") (pin "2") (pinfunction "2_2") (pintype "passive"))
      (node (ref "R18") (pin "2") (pinfunction "2_2") (pintype "passive"))
      (node (ref "R24") (pin "2") (pinfunction "2_2") (pintype "passive"))
    )
    (net (code "43") (name "Net-(IC5D-IN)") (class "Default")
      (node (ref "IC5") (pin "15") (pinfunction "IN_15") (pintype "input"))
      (node (ref "R10") (pin "1") (pinfunction "1_1") (pintype "passive"))
      (node (ref "R16") (pin "2") (pinfunction "2_2") (pintype "passive"))
      (node (ref "R21") (pin "2") (pinfunction "2_2") (pintype "passive"))
    )
    (net (code "44") (name "Net-(IC6A--IN)") (class "Default")
      (node (ref "IC6") (pin "2") (pinfunction "-IN_2") (pintype "input"))
      (node (ref "R35") (pin "1") (pinfunction "1_1") (pintype "passive"))
      (node (ref "R37") (pin "2") (pinfunction "2_2") (pintype "passive"))
      (node (ref "R38") (pin "1") (pinfunction "1_1") (pintype "passive"))
      (node (ref "R40") (pin "1") (pinfunction "1_1") (pintype "passive"))
    )
    (net (code "45") (name "Net-(IC6B--IN)") (class "Default")
      (node (ref "C25") (pin "1") (pinfunction "1_1") (pintype "passive"))
      (node (ref "IC6") (pin "6") (pinfunction "-IN_6") (pintype "input"))
      (node (ref "IC8") (pin "4") (pinfunction "OUT_4") (pintype "output"))
    )
    (net (code "46") (name "Net-(IC6C--IN)") (class "Default")
      (node (ref "C26") (pin "1") (pinfunction "1_1") (pintype "passive"))
      (node (ref "IC6") (pin "9") (pinfunction "-IN_9") (pintype "input"))
      (node (ref "IC8") (pin "13") (pinfunction "OUT_13") (pintype "output"))
    )
    (net (code "47") (name "Net-(IC6C-OUT)") (class "Default")
      (node (ref "C26") (pin "2") (pinfunction "2_2") (pintype "passive"))
      (node (ref "IC6") (pin "8") (pinfunction "OUT_8") (pintype "output"))
      (node (ref "JP5") (pin "2") (pinfunction "2_2") (pintype "passive"))
      (node (ref "R35") (pin "2") (pinfunction "2_2") (pintype "passive"))
    )
    (net (code "48") (name "Net-(IC6D--IN)") (class "Default")
      (node (ref "IC6") (pin "13") (pinfunction "-IN_13") (pintype "input"))
      (node (ref "IC8") (pin "5") (pinfunction "OUT_5") (pintype "output"))
      (node (ref "R41") (pin "2") (pinfunction "2_2") (pintype "passive"))
    )
    (net (code "49") (name "Net-(IC6D-OUT)") (class "Default")
      (node (ref "IC6") (pin "14") (pinfunction "OUT_14") (pintype "output"))
      (node (ref "R38") (pin "2") (pinfunction "2_2") (pintype "passive"))
      (node (ref "R39") (pin "1") (pinfunction "1_1") (pintype "passive"))
      (node (ref "R55") (pin "1") (pinfunction "1_1") (pintype "passive"))
      (node (ref "R67") (pin "1") (pinfunction "1_1") (pintype "passive"))
    )
    (net (code "50") (name "Net-(IC7A--IN)") (class "Default")
      (node (ref "C23") (pin "2") (pinfunction "2_2") (pintype "passive"))
      (node (ref "IC7") (pin "2") (pinfunction "-IN_2") (pintype "input"))
      (node (ref "R36") (pin "P$3") (pinfunction "A_P$3") (pintype "passive"))
      (node (ref "R44") (pin "2") (pinfunction "2_2") (pintype "passive"))
      (node (ref "R45") (pin "2") (pinfunction "2_2") (pintype "passive"))
      (node (ref "R46") (pin "2") (pinfunction "2_2") (pintype "passive"))
      (node (ref "R50") (pin "1") (pinfunction "1_1") (pintype "passive"))
    )
    (net (code "51") (name "Net-(IC7A-OUT)") (class "Default")
      (node (ref "C23") (pin "1") (pinfunction "1_1") (pintype "passive"))
      (node (ref "D7") (pin "C") (pinfunction "C_C") (pintype "passive"))
      (node (ref "IC7") (pin "1") (pinfunction "OUT_1") (pintype "output"))
      (node (ref "IC8") (pin "11") (pinfunction "CTRL_11") (pintype "input"))
      (node (ref "R50") (pin "2") (pinfunction "2_2") (pintype "passive"))
    )
    (net (code "52") (name "Net-(IC7B--IN)") (class "Default")
      (node (ref "IC7") (pin "6") (pinfunction "-IN_6") (pintype "input"))
      (node (ref "R58") (pin "2") (pinfunction "2_2") (pintype "passive"))
      (node (ref "R59") (pin "1") (pinfunction "1_1") (pintype "passive"))
    )
    (net (code "53") (name "Net-(IC7B-OUT)") (class "Default")
      (node (ref "IC7") (pin "7") (pinfunction "OUT_7") (pintype "output"))
      (node (ref "R59") (pin "2") (pinfunction "2_2") (pintype "passive"))
      (node (ref "R62") (pin "1") (pinfunction "1_1") (pintype "passive"))
    )
    (net (code "54") (name "Net-(IC7C--IN)") (class "Default")
      (node (ref "C32") (pin "2") (pinfunction "2_2") (pintype "passive"))
      (node (ref "IC7") (pin "9") (pinfunction "-IN_9") (pintype "input"))
      (node (ref "R42") (pin "P$1") (pinfunction "E_P$1") (pintype "passive"))
      (node (ref "R60") (pin "1") (pinfunction "1_1") (pintype "passive"))
      (node (ref "R62") (pin "2") (pinfunction "2_2") (pintype "passive"))
      (node (ref "R63") (pin "2") (pinfunction "2_2") (pintype "passive"))
    )
    (net (code "55") (name "Net-(IC7C-OUT)") (class "Default")
      (node (ref "C32") (pin "1") (pinfunction "1_1") (pintype "passive"))
      (node (ref "D9") (pin "C") (pinfunction "C_C") (pintype "passive"))
      (node (ref "IC7") (pin "8") (pinfunction "OUT_8") (pintype "output"))
      (node (ref "IC8") (pin "6") (pinfunction "CTRL_6") (pintype "input"))
      (node (ref "R60") (pin "2") (pinfunction "2_2") (pintype "passive"))
    )
    (net (code "56") (name "Net-(IC7D--IN)") (class "Default")
      (node (ref "C24") (pin "2") (pinfunction "2_2") (pintype "passive"))
      (node (ref "D8") (pin "A") (pinfunction "A_A") (pintype "passive"))
      (node (ref "IC7") (pin "13") (pinfunction "-IN_13") (pintype "input"))
      (node (ref "R34") (pin "P$3") (pinfunction "A_P$3") (pintype "passive"))
      (node (ref "R47") (pin "2") (pinfunction "2_2") (pintype "passive"))
      (node (ref "R48") (pin "2") (pinfunction "2_2") (pintype "passive"))
      (node (ref "R51") (pin "1") (pinfunction "1_1") (pintype "passive"))
    )
    (net (code "57") (name "Net-(IC7D-OUT)") (class "Default")
      (node (ref "D15") (pin "A") (pinfunction "A_A") (pintype "passive"))
      (node (ref "D8") (pin "C") (pinfunction "C_C") (pintype "passive"))
      (node (ref "IC7") (pin "14") (pinfunction "OUT_14") (pintype "output"))
    )
    (net (code "58") (name "Net-(IC8A-CTRL)") (class "Default")
      (node (ref "C24") (pin "1") (pinfunction "1_1") (pintype "passive"))
      (node (ref "D15") (pin "C") (pinfunction "C_C") (pintype "passive"))
      (node (ref "IC8") (pin "14") (pinfunction "CTRL_14") (pintype "input"))
      (node (ref "IC8") (pin "3") (pinfunction "CTRL_3") (pintype "input"))
      (node (ref "R51") (pin "2") (pinfunction "2_2") (pintype "passive"))
    )
    (net (code "59") (name "Net-(IC8A-IN)") (class "Default")
      (node (ref "IC8") (pin "2") (pinfunction "IN_2") (pintype "input"))
      (node (ref "R52") (pin "2") (pinfunction "2_2") (pintype "passive"))
      (node (ref "R56") (pin "2") (pinfunction "2_2") (pintype "passive"))
    )
    (net (code "60") (name "Net-(IC8B-IN)") (class "Default")
      (node (ref "IC8") (pin "7") (pinfunction "IN_7") (pintype "input"))
      (node (ref "R61") (pin "2") (pinfunction "2_2") (pintype "passive"))
      (node (ref "R66") (pin "2") (pinfunction "2_2") (pintype "passive"))
    )
    (net (code "61") (name "Net-(IC8C-IN)") (class "Default")
      (node (ref "IC8") (pin "10") (pinfunction "IN_10") (pintype "input"))
      (node (ref "R64") (pin "2") (pinfunction "2_2") (pintype "passive"))
      (node (ref "R67") (pin "2") (pinfunction "2_2") (pintype "passive"))
    )
    (net (code "62") (name "Net-(IC8D-IN)") (class "Default")
      (node (ref "IC8") (pin "15") (pinfunction "IN_15") (pintype "input"))
      (node (ref "R53") (pin "2") (pinfunction "2_2") (pintype "passive"))
      (node (ref "R57") (pin "2") (pinfunction "2_2") (pintype "passive"))
    )
    (net (code "63") (name "Net-(IC9A--IN)") (class "Default")
      (node (ref "IC9") (pin "2") (pinfunction "-IN_2") (pintype "input"))
      (node (ref "R71") (pin "1") (pinfunction "1_1") (pintype "passive"))
      (node (ref "R72") (pin "2") (pinfunction "2_2") (pintype "passive"))
      (node (ref "R73") (pin "1") (pinfunction "1_1") (pintype "passive"))
      (node (ref "R75") (pin "1") (pinfunction "1_1") (pintype "passive"))
    )
    (net (code "64") (name "Net-(IC9C-OUT)") (class "Default")
      (node (ref "C41") (pin "2") (pinfunction "2_2") (pintype "passive"))
      (node (ref "IC9") (pin "8") (pinfunction "OUT_8") (pintype "output"))
      (node (ref "JP13") (pin "2") (pinfunction "2_2") (pintype "passive"))
      (node (ref "R71") (pin "2") (pinfunction "2_2") (pintype "passive"))
    )
    (net (code "65") (name "Net-(IC9D-OUT)") (class "Default")
      (node (ref "IC9") (pin "14") (pinfunction "OUT_14") (pintype "output"))
      (node (ref "R73") (pin "2") (pinfunction "2_2") (pintype "passive"))
      (node (ref "R74") (pin "1") (pinfunction "1_1") (pintype "passive"))
      (node (ref "R88") (pin "1") (pinfunction "1_1") (pintype "passive"))
      (node (ref "R99") (pin "1") (pinfunction "1_1") (pintype "passive"))
    )
    (net (code "66") (name "Net-(IC10A--IN)") (class "Default")
      (node (ref "C38") (pin "2") (pinfunction "2_2") (pintype "passive"))
      (node (ref "IC10") (pin "2") (pinfunction "-IN_2") (pintype "input"))
      (node (ref "R69") (pin "P$3") (pinfunction "A_P$3") (pintype "passive"))
      (node (ref "R78") (pin "2") (pinfunction "2_2") (pintype "passive"))
      (node (ref "R79") (pin "2") (pinfunction "2_2") (pintype "passive"))
      (node (ref "R80") (pin "2") (pinfunction "2_2") (pintype "passive"))
      (node (ref "R84") (pin "1") (pinfunction "1_1") (pintype "passive"))
    )
    (net (code "67") (name "Net-(IC10A-OUT)") (class "Default")
      (node (ref "C38") (pin "1") (pinfunction "1_1") (pintype "passive"))
      (node (ref "D10") (pin "C") (pinfunction "C_C") (pintype "passive"))
      (node (ref "IC10") (pin "1") (pinfunction "OUT_1") (pintype "output"))
      (node (ref "IC11") (pin "11") (pinfunction "CTRL_11") (pintype "input"))
      (node (ref "R84") (pin "2") (pinfunction "2_2") (pintype "passive"))
    )
    (net (code "68") (name "Net-(IC10B--IN)") (class "Default")
      (node (ref "IC10") (pin "6") (pinfunction "-IN_6") (pintype "input"))
      (node (ref "R91") (pin "2") (pinfunction "2_2") (pintype "passive"))
      (node (ref "R92") (pin "1") (pinfunction "1_1") (pintype "passive"))
    )
    (net (code "69") (name "Net-(IC10B-OUT)") (class "Default")
      (node (ref "IC10") (pin "7") (pinfunction "OUT_7") (pintype "output"))
      (node (ref "R92") (pin "2") (pinfunction "2_2") (pintype "passive"))
      (node (ref "R95") (pin "1") (pinfunction "1_1") (pintype "passive"))
    )
    (net (code "70") (name "Net-(IC10C--IN)") (class "Default")
      (node (ref "C46") (pin "2") (pinfunction "2_2") (pintype "passive"))
      (node (ref "IC10") (pin "9") (pinfunction "-IN_9") (pintype "input"))
      (node (ref "R65") (pin "P$1") (pinfunction "E_P$1") (pintype "passive"))
      (node (ref "R93") (pin "1") (pinfunction "1_1") (pintype "passive"))
      (node (ref "R95") (pin "2") (pinfunction "2_2") (pintype "passive"))
      (node (ref "R96") (pin "2") (pinfunction "2_2") (pintype "passive"))
    )
    (net (code "71") (name "Net-(IC10C-OUT)") (class "Default")
      (node (ref "C46") (pin "1") (pinfunction "1_1") (pintype "passive"))
      (node (ref "D12") (pin "C") (pinfunction "C_C") (pintype "passive"))
      (node (ref "IC10") (pin "8") (pinfunction "OUT_8") (pintype "output"))
      (node (ref "IC11") (pin "6") (pinfunction "CTRL_6") (pintype "input"))
      (node (ref "R93") (pin "2") (pinfunction "2_2") (pintype "passive"))
    )
    (net (code "72") (name "Net-(IC10D--IN)") (class "Default")
      (node (ref "C39") (pin "2") (pinfunction "2_2") (pintype "passive"))
      (node (ref "D11") (pin "A") (pinfunction "A_A") (pintype "passive"))
      (node (ref "IC10") (pin "13") (pinfunction "-IN_13") (pintype "input"))
      (node (ref "R68") (pin "P$3") (pinfunction "A_P$3") (pintype "passive"))
      (node (ref "R81") (pin "2") (pinfunction "2_2") (pintype "passive"))
      (node (ref "R82") (pin "2") (pinfunction "2_2") (pintype "passive"))
      (node (ref "R85") (pin "1") (pinfunction "1_1") (pintype "passive"))
    )
    (net (code "73") (name "Net-(IC10D-OUT)") (class "Default")
      (node (ref "D11") (pin "C") (pinfunction "C_C") (pintype "passive"))
      (node (ref "D16") (pin "A") (pinfunction "A_A") (pintype "passive"))
      (node (ref "IC10") (pin "14") (pinfunction "OUT_14") (pintype "output"))
    )
    (net (code "74") (name "Net-(IC11A-CTRL)") (class "Default")
      (node (ref "C39") (pin "1") (pinfunction "1_1") (pintype "passive"))
      (node (ref "D16") (pin "C") (pinfunction "C_C") (pintype "passive"))
      (node (ref "IC11") (pin "14") (pinfunction "CTRL_14") (pintype "input"))
      (node (ref "IC11") (pin "3") (pinfunction "CTRL_3") (pintype "input"))
      (node (ref "R85") (pin "2") (pinfunction "2_2") (pintype "passive"))
    )
    (net (code "75") (name "Net-(IC11A-IN)") (class "Default")
      (node (ref "IC11") (pin "2") (pinfunction "IN_2") (pintype "input"))
      (node (ref "R86") (pin "2") (pinfunction "2_2") (pintype "passive"))
      (node (ref "R89") (pin "2") (pinfunction "2_2") (pintype "passive"))
    )
    (net (code "76") (name "Net-(IC11A-OUT)") (class "Default")
      (node (ref "C40") (pin "1") (pinfunction "1_1") (pintype "passive"))
      (node (ref "IC11") (pin "4") (pinfunction "OUT_4") (pintype "output"))
      (node (ref "IC9") (pin "6") (pinfunction "-IN_6") (pintype "input"))
    )
    (net (code "77") (name "Net-(IC11B-IN)") (class "Default")
      (node (ref "IC11") (pin "7") (pinfunction "IN_7") (pintype "input"))
      (node (ref "R94") (pin "2") (pinfunction "2_2") (pintype "passive"))
      (node (ref "R98") (pin "2") (pinfunction "2_2") (pintype "passive"))
    )
    (net (code "78") (name "Net-(IC11B-OUT)") (class "Default")
      (node (ref "IC11") (pin "5") (pinfunction "OUT_5") (pintype "output"))
      (node (ref "IC9") (pin "13") (pinfunction "-IN_13") (pintype "input"))
      (node (ref "R76") (pin "2") (pinfunction "2_2") (pintype "passive"))
    )
    (net (code "79") (name "Net-(IC11C-IN)") (class "Default")
      (node (ref "IC11") (pin "10") (pinfunction "IN_10") (pintype "input"))
      (node (ref "R97") (pin "2") (pinfunction "2_2") (pintype "passive"))
      (node (ref "R99") (pin "2") (pinfunction "2_2") (pintype "passive"))
    )
    (net (code "80") (name "Net-(IC11D-IN)") (class "Default")
      (node (ref "IC11") (pin "15") (pinfunction "IN_15") (pintype "input"))
      (node (ref "R87") (pin "2") (pinfunction "2_2") (pintype "passive"))
      (node (ref "R90") (pin "2") (pinfunction "2_2") (pintype "passive"))
    )
    (net (code "81") (name "Net-(IC11D-OUT)") (class "Default")
      (node (ref "C41") (pin "1") (pinfunction "1_1") (pintype "passive"))
      (node (ref "IC11") (pin "13") (pinfunction "OUT_13") (pintype "output"))
      (node (ref "IC9") (pin "9") (pinfunction "-IN_9") (pintype "input"))
    )
    (net (code "82") (name "Net-(IC12A--IN)") (class "Default")
      (node (ref "IC12") (pin "2") (pinfunction "-IN_2") (pintype "input"))
      (node (ref "R102") (pin "1") (pinfunction "1_1") (pintype "passive"))
      (node (ref "R105") (pin "2") (pinfunction "2_2") (pintype "passive"))
    )
    (net (code "83") (name "Net-(IC12A-OUT)") (class "Default")
      (node (ref "IC12") (pin "1") (pinfunction "OUT_1") (pintype "output"))
      (node (ref "R102") (pin "2") (pinfunction "2_2") (pintype "passive"))
      (node (ref "R106") (pin "1") (pinfunction "1_1") (pintype "passive"))
    )
    (net (code "84") (name "Net-(IC12B--IN)") (class "Default")
      (node (ref "IC12") (pin "6") (pinfunction "-IN_6") (pintype "input"))
      (node (ref "R103") (pin "1") (pinfunction "1_1") (pintype "passive"))
      (node (ref "R106") (pin "2") (pinfunction "2_2") (pintype "passive"))
      (node (ref "R122") (pin "1") (pinfunction "1_1") (pintype "passive"))
    )
    (net (code "85") (name "Net-(IC13B-OUT)") (class "Default")
      (node (ref "IC13") (pin "7") (pinfunction "OUT_7") (pintype "output"))
      (node (ref "R104") (pin "1") (pinfunction "1_1") (pintype "passive"))
      (node (ref "R110") (pin "2") (pinfunction "2_2") (pintype "passive"))
    )
    (net (code "86") (name "Net-(IC14A-+IN)") (class "Default")
      (node (ref "IC14") (pin "3") (pinfunction "+IN_3") (pintype "input"))
      (node (ref "IC14") (pin "6") (pinfunction "-IN_6") (pintype "input"))
      (node (ref "R115") (pin "2") (pinfunction "2_2") (pintype "passive"))
      (node (ref "R117") (pin "2") (pinfunction "2_2") (pintype "passive"))
      (node (ref "R118") (pin "1") (pinfunction "1_1") (pintype "passive"))
    )
    (net (code "87") (name "Net-(IC14A--IN)") (class "Default")
      (node (ref "IC14") (pin "2") (pinfunction "-IN_2") (pintype "input"))
      (node (ref "R119") (pin "2") (pinfunction "2_2") (pintype "passive"))
      (node (ref "R121") (pin "1") (pinfunction "1_1") (pintype "passive"))
    )
    (net (code "88") (name "Net-(IC14A-OUT)") (class "Default")
      (node (ref "D13") (pin "A") (pinfunction "A_A") (pintype "passive"))
      (node (ref "IC14") (pin "1") (pinfunction "OUT_1") (pintype "output"))
    )
    (net (code "89") (name "Net-(IC14B-+IN)") (class "Default")
      (node (ref "IC14") (pin "5") (pinfunction "+IN_5") (pintype "input"))
      (node (ref "R119") (pin "1") (pinfunction "1_1") (pintype "passive"))
      (node (ref "R120") (pin "2") (pinfunction "2_2") (pintype "passive"))
    )
    (net (code "90") (name "Net-(IC14B-OUT)") (class "Default")
      (node (ref "D14") (pin "A") (pinfunction "A_A") (pintype "passive"))
      (node (ref "IC14") (pin "7") (pinfunction "OUT_7") (pintype "output"))
    )
    (net (code "91") (name "Net-(J1-3)") (class "Default")
      (node (ref "J1") (pin "P3") (pinfunction "3_P3") (pintype "passive"))
      (node (ref "R6") (pin "1") (pinfunction "1_1") (pintype "passive"))
    )
    (net (code "92") (name "Net-(J2-3)") (class "Default")
      (node (ref "J2") (pin "P3") (pinfunction "3_P3") (pintype "passive"))
      (node (ref "R30") (pin "1") (pinfunction "1_1") (pintype "passive"))
    )
    (net (code "93") (name "Net-(J3-3)") (class "Default")
      (node (ref "J3") (pin "P3") (pinfunction "3_P3") (pintype "passive"))
      (node (ref "R48") (pin "1") (pinfunction "1_1") (pintype "passive"))
    )
    (net (code "94") (name "Net-(J4-3)") (class "Default")
      (node (ref "J4") (pin "P3") (pinfunction "3_P3") (pintype "passive"))
      (node (ref "R45") (pin "1") (pinfunction "1_1") (pintype "passive"))
    )
    (net (code "95") (name "Net-(J5-3)") (class "Default")
      (node (ref "J5") (pin "P3") (pinfunction "3_P3") (pintype "passive"))
      (node (ref "R58") (pin "1") (pinfunction "1_1") (pintype "passive"))
    )
    (net (code "96") (name "Net-(J6-3)") (class "Default")
      (node (ref "J6") (pin "P3") (pinfunction "3_P3") (pintype "passive"))
      (node (ref "R91") (pin "1") (pinfunction "1_1") (pintype "passive"))
    )
    (net (code "97") (name "Net-(J7-3)") (class "Default")
      (node (ref "J7") (pin "P3") (pinfunction "3_P3") (pintype "passive"))
      (node (ref "R82") (pin "1") (pinfunction "1_1") (pintype "passive"))
    )
    (net (code "98") (name "Net-(J8-3)") (class "Default")
      (node (ref "J8") (pin "P3") (pinfunction "3_P3") (pintype "passive"))
      (node (ref "R78") (pin "1") (pinfunction "1_1") (pintype "passive"))
    )
    (net (code "99") (name "Net-(J9-3)") (class "Default")
      (node (ref "J9") (pin "P3") (pinfunction "3_P3") (pintype "passive"))
      (node (ref "R9") (pin "1") (pinfunction "1_1") (pintype "passive"))
    )
    (net (code "100") (name "Net-(J10-3)") (class "Default")
      (node (ref "J10") (pin "P3") (pinfunction "3_P3") (pintype "passive"))
      (node (ref "R27") (pin "1") (pinfunction "1_1") (pintype "passive"))
    )
    (net (code "101") (name "Net-(J13-3)") (class "Default")
      (node (ref "J13") (pin "P3") (pinfunction "3_P3") (pintype "passive"))
      (node (ref "R105") (pin "1") (pinfunction "1_1") (pintype "passive"))
    )
    (net (code "102") (name "Net-(J14-3)") (class "Default")
      (node (ref "J14") (pin "P3") (pinfunction "3_P3") (pintype "passive"))
      (node (ref "R111") (pin "2") (pinfunction "2_2") (pintype "passive"))
    )
    (net (code "103") (name "Net-(JP11-Pad10)") (class "Default")
      (node (ref "JP11") (pin "10") (pinfunction "10_10") (pintype "passive"))
      (node (ref "JP11") (pin "9") (pinfunction "9_9") (pintype "passive"))
      (node (ref "P1") (pin "2") (pinfunction "2_2") (pintype "bidirectional"))
    )
    (net (code "104") (name "Net-(JP12-Pad2)") (class "Default")
      (node (ref "JP12") (pin "2") (pinfunction "2_2") (pintype "passive"))
      (node (ref "R122") (pin "2") (pinfunction "2_2") (pintype "passive"))
    )
    (net (code "105") (name "Net-(LED1-C)") (class "Default")
      (node (ref "LED1") (pin "K") (pinfunction "C_K") (pintype "passive"))
      (node (ref "Q1") (pin "C") (pinfunction "C_C") (pintype "passive"))
    )
    (net (code "106") (name "Net-(LED1-PadA)") (class "Default")
      (node (ref "LED1") (pin "A") (pinfunction "A_A") (pintype "passive"))
      (node (ref "R112") (pin "1") (pinfunction "1_1") (pintype "passive"))
    )
    (net (code "107") (name "Net-(Q1-PadB)") (class "Default")
      (node (ref "Q1") (pin "B") (pinfunction "B_B") (pintype "passive"))
      (node (ref "R114") (pin "2") (pinfunction "2_2") (pintype "passive"))
      (node (ref "R116") (pin "2") (pinfunction "2_2") (pintype "passive"))
    )
    (net (code "108") (name "Net-(R3-S)") (class "Default")
      (node (ref "R3") (pin "P$2") (pinfunction "S_P$2") (pintype "passive"))
      (node (ref "R5") (pin "2") (pinfunction "2_2") (pintype "passive"))
    )
    (net (code "109") (name "Net-(R4-S)") (class "Default")
      (node (ref "R12") (pin "2") (pinfunction "2_2") (pintype "passive"))
      (node (ref "R4") (pin "P$2") (pinfunction "S_P$2") (pintype "passive"))
    )
    (net (code "110") (name "Net-(R34-S)") (class "Default")
      (node (ref "R34") (pin "P$2") (pinfunction "S_P$2") (pintype "passive"))
      (node (ref "R43") (pin "2") (pinfunction "2_2") (pintype "passive"))
    )
    (net (code "111") (name "Net-(R36-S)") (class "Default")
      (node (ref "R36") (pin "P$2") (pinfunction "S_P$2") (pintype "passive"))
      (node (ref "R49") (pin "2") (pinfunction "2_2") (pintype "passive"))
    )
    (net (code "112") (name "Net-(R39-Pad2)") (class "Default")
      (node (ref "R39") (pin "2") (pinfunction "2_2") (pintype "passive"))
      (node (ref "R41") (pin "1") (pinfunction "1_1") (pintype "passive"))
    )
    (net (code "113") (name "Net-(R42-S)") (class "Default")
      (node (ref "R42") (pin "P$2") (pinfunction "S_P$2") (pintype "passive"))
      (node (ref "R54") (pin "2") (pinfunction "2_2") (pintype "passive"))
    )
    (net (code "114") (name "Net-(R65-S)") (class "Default")
      (node (ref "R65") (pin "P$2") (pinfunction "S_P$2") (pintype "passive"))
      (node (ref "R70") (pin "2") (pinfunction "2_2") (pintype "passive"))
    )
    (net (code "115") (name "Net-(R68-S)") (class "Default")
      (node (ref "R68") (pin "P$2") (pinfunction "S_P$2") (pintype "passive"))
      (node (ref "R77") (pin "2") (pinfunction "2_2") (pintype "passive"))
    )
    (net (code "116") (name "Net-(R69-S)") (class "Default")
      (node (ref "R69") (pin "P$2") (pinfunction "S_P$2") (pintype "passive"))
      (node (ref "R83") (pin "2") (pinfunction "2_2") (pintype "passive"))
    )
    (net (code "117") (name "Net-(R74-Pad2)") (class "Default")
      (node (ref "R74") (pin "2") (pinfunction "2_2") (pintype "passive"))
      (node (ref "R76") (pin "1") (pinfunction "1_1") (pintype "passive"))
    )
    (net (code "118") (name "Net-(R100-S)") (class "Default")
      (node (ref "R100") (pin "P$2") (pinfunction "S_P$2") (pintype "passive"))
      (node (ref "R109") (pin "2") (pinfunction "2_2") (pintype "passive"))
    )
    (net (code "119") (name "Net-(R101-S)") (class "Default")
      (node (ref "R101") (pin "P$2") (pinfunction "S_P$2") (pintype "passive"))
      (node (ref "R108") (pin "2") (pinfunction "2_2") (pintype "passive"))
    )
    (net (code "120") (name "OUTPUT") (class "Default")
      (node (ref "C57") (pin "2") (pinfunction "2_2") (pintype "passive"))
      (node (ref "IC13") (pin "1") (pinfunction "OUT_1") (pintype "output"))
      (node (ref "R107") (pin "2") (pinfunction "2_2") (pintype "passive"))
      (node (ref "R111") (pin "1") (pinfunction "1_1") (pintype "passive"))
    )
    (net (code "121") (name "PLUS_BUS") (class "Default")
      (node (ref "IC13") (pin "6") (pinfunction "-IN_6") (pintype "input"))
      (node (ref "IC5") (pin "12") (pinfunction "OUT_12") (pintype "output"))
      (node (ref "R110") (pin "1") (pinfunction "1_1") (pintype "passive"))
      (node (ref "R33") (pin "2") (pinfunction "2_2") (pintype "passive"))
      (node (ref "R55") (pin "2") (pinfunction "2_2") (pintype "passive"))
      (node (ref "R88") (pin "2") (pinfunction "2_2") (pintype "passive"))
    )
    (net (code "122") (name "VCC") (class "Default")
      (node (ref "C1") (pin "+") (pinfunction "+_+") (pintype "passive"))
      (node (ref "C12") (pin "1") (pinfunction "1_1") (pintype "passive"))
      (node (ref "C21") (pin "1") (pinfunction "1_1") (pintype "passive"))
      (node (ref "C27") (pin "1") (pinfunction "1_1") (pintype "passive"))
      (node (ref "C31") (pin "1") (pinfunction "1_1") (pintype "passive"))
      (node (ref "C36") (pin "1") (pinfunction "1_1") (pintype "passive"))
      (node (ref "C42") (pin "1") (pinfunction "1_1") (pintype "passive"))
      (node (ref "C43") (pin "1") (pinfunction "1_1") (pintype "passive"))
      (node (ref "C5") (pin "1") (pinfunction "1_1") (pintype "passive"))
      (node (ref "C50") (pin "1") (pinfunction "1_1") (pintype "passive"))
      (node (ref "C52") (pin "1") (pinfunction "1_1") (pintype "passive"))
      (node (ref "C56") (pin "1") (pinfunction "1_1") (pintype "passive"))
      (node (ref "C58") (pin "+") (pinfunction "+_+") (pintype "passive"))
      (node (ref "C9") (pin "1") (pinfunction "1_1") (pintype "passive"))
      (node (ref "D2") (pin "C") (pinfunction "C_C") (pintype "passive"))
      (node (ref "IC10") (pin "4") (pinfunction "V+_4") (pintype "power_in"))
      (node (ref "IC11") (pin "16") (pinfunction "V+_16") (pintype "power_in"))
      (node (ref "IC12") (pin "8") (pinfunction "V+_8") (pintype "power_in"))
      (node (ref "IC13") (pin "8") (pinfunction "V+_8") (pintype "power_in"))
      (node (ref "IC14") (pin "8") (pinfunction "V+_8") (pintype "power_in"))
      (node (ref "IC3") (pin "8") (pinfunction "V+_8") (pintype "power_in"))
      (node (ref "IC4") (pin "4") (pinfunction "V+_4") (pintype "power_in"))
      (node (ref "IC5") (pin "16") (pinfunction "V+_16") (pintype "power_in"))
      (node (ref "IC6") (pin "4") (pinfunction "V+_4") (pintype "power_in"))
      (node (ref "IC7") (pin "4") (pinfunction "V+_4") (pintype "power_in"))
      (node (ref "IC8") (pin "16") (pinfunction "V+_16") (pintype "power_in"))
      (node (ref "IC9") (pin "4") (pinfunction "V+_4") (pintype "power_in"))
      (node (ref "R1") (pin "1") (pinfunction "1_1") (pintype "passive"))
      (node (ref "R112") (pin "2") (pinfunction "2_2") (pintype "passive"))
    )
    (net (code "123") (name "VEE") (class "Default")
      (node (ref "C13") (pin "2") (pinfunction "2_2") (pintype "passive"))
      (node (ref "C2") (pin "-") (pinfunction "-_-") (pintype "passive"))
      (node (ref "C20") (pin "2") (pinfunction "2_2") (pintype "passive"))
      (node (ref "C22") (pin "2") (pinfunction "2_2") (pintype "passive"))
      (node (ref "C28") (pin "2") (pinfunction "2_2") (pintype "passive"))
      (node (ref "C35") (pin "2") (pinfunction "2_2") (pintype "passive"))
      (node (ref "C37") (pin "2") (pinfunction "2_2") (pintype "passive"))
      (node (ref "C44") (pin "2") (pinfunction "2_2") (pintype "passive"))
      (node (ref "C51") (pin "2") (pinfunction "2_2") (pintype "passive"))
      (node (ref "C53") (pin "2") (pinfunction "2_2") (pintype "passive"))
      (node (ref "C54") (pin "2") (pinfunction "2_2") (pintype "passive"))
      (node (ref "C8") (pin "2") (pinfunction "2_2") (pintype "passive"))
      (node (ref "D1") (pin "A") (pinfunction "A_A") (pintype "passive"))
      (node (ref "IC10") (pin "11") (pinfunction "V-_11") (pintype "power_in"))
      (node (ref "IC11") (pin "9") (pinfunction "V-_9") (pintype "power_in"))
      (node (ref "IC12") (pin "4") (pinfunction "V-_4") (pintype "power_in"))
      (node (ref "IC13") (pin "4") (pinfunction "V-_4") (pintype "power_in"))
      (node (ref "IC3") (pin "4") (pinfunction "V-_4") (pintype "power_in"))
      (node (ref "IC4") (pin "11") (pinfunction "V-_11") (pintype "power_in"))
      (node (ref "IC5") (pin "9") (pinfunction "V-_9") (pintype "power_in"))
      (node (ref "IC6") (pin "11") (pinfunction "V-_11") (pintype "power_in"))
      (node (ref "IC7") (pin "11") (pinfunction "V-_11") (pintype "power_in"))
      (node (ref "IC8") (pin "9") (pinfunction "V-_9") (pintype "power_in"))
      (node (ref "IC9") (pin "11") (pinfunction "V-_11") (pintype "power_in"))
      (node (ref "P1") (pin "1") (pinfunction "1_1") (pintype "bidirectional"))
      (node (ref "R2") (pin "1") (pinfunction "1_1") (pintype "passive"))
    )
    (net (code "124") (name "unconnected-(IC5E-MODE-Pad1)") (class "Default")
      (node (ref "IC5") (pin "1") (pinfunction "MODE_1") (pintype "input"))
    )
    (net (code "125") (name "unconnected-(IC8E-MODE-Pad1)") (class "Default")
      (node (ref "IC8") (pin "1") (pinfunction "MODE_1") (pintype "input"))
    )
    (net (code "126") (name "unconnected-(IC11E-MODE-Pad1)") (class "Default")
      (node (ref "IC11") (pin "1") (pinfunction "MODE_1") (pintype "input"))
    )
    (net (code "127") (name "unconnected-(J1-2-PadP2)") (class "Default")
      (node (ref "J1") (pin "P2") (pinfunction "2_P2") (pintype "passive"))
    )
    (net (code "128") (name "unconnected-(J2-2-PadP2)") (class "Default")
      (node (ref "J2") (pin "P2") (pinfunction "2_P2") (pintype "passive"))
    )
    (net (code "129") (name "unconnected-(J3-2-PadP2)") (class "Default")
      (node (ref "J3") (pin "P2") (pinfunction "2_P2") (pintype "passive"))
    )
    (net (code "130") (name "unconnected-(J4-2-PadP2)") (class "Default")
      (node (ref "J4") (pin "P2") (pinfunction "2_P2") (pintype "passive"))
    )
    (net (code "131") (name "unconnected-(J5-2-PadP2)") (class "Default")
      (node (ref "J5") (pin "P2") (pinfunction "2_P2") (pintype "passive"))
    )
    (net (code "132") (name "unconnected-(J6-2-PadP2)") (class "Default")
      (node (ref "J6") (pin "P2") (pinfunction "2_P2") (pintype "passive"))
    )
    (net (code "133") (name "unconnected-(J7-2-PadP2)") (class "Default")
      (node (ref "J7") (pin "P2") (pinfunction "2_P2") (pintype "passive"))
    )
    (net (code "134") (name "unconnected-(J8-2-PadP2)") (class "Default")
      (node (ref "J8") (pin "P2") (pinfunction "2_P2") (pintype "passive"))
    )
    (net (code "135") (name "unconnected-(J9-2-PadP2)") (class "Default")
      (node (ref "J9") (pin "P2") (pinfunction "2_P2") (pintype "passive"))
    )
    (net (code "136") (name "unconnected-(J10-2-PadP2)") (class "Default")
      (node (ref "J10") (pin "P2") (pinfunction "2_P2") (pintype "passive"))
    )
    (net (code "137") (name "unconnected-(J11-2-PadP2)") (class "Default")
      (node (ref "J11") (pin "P2") (pinfunction "2_P2") (pintype "passive"))
    )
    (net (code "138") (name "unconnected-(J12-2-PadP2)") (class "Default")
      (node (ref "J12") (pin "P2") (pinfunction "2_P2") (pintype "passive"))
    )
    (net (code "139") (name "unconnected-(J13-2-PadP2)") (class "Default")
      (node (ref "J13") (pin "P2") (pinfunction "2_P2") (pintype "passive"))
    )
    (net (code "140") (name "unconnected-(J14-2-PadP2)") (class "Default")
      (node (ref "J14") (pin "P2") (pinfunction "2_P2") (pintype "passive"))
    )
    (net (code "141") (name "unconnected-(JP12-Pad1)") (class "Default")
      (node (ref "JP12") (pin "1") (pinfunction "1_1") (pintype "passive"))
    )
  )
)
